# FPGA_ADC_USB_Board.net
KiCad netlist of a schematic drawn in EAGLE
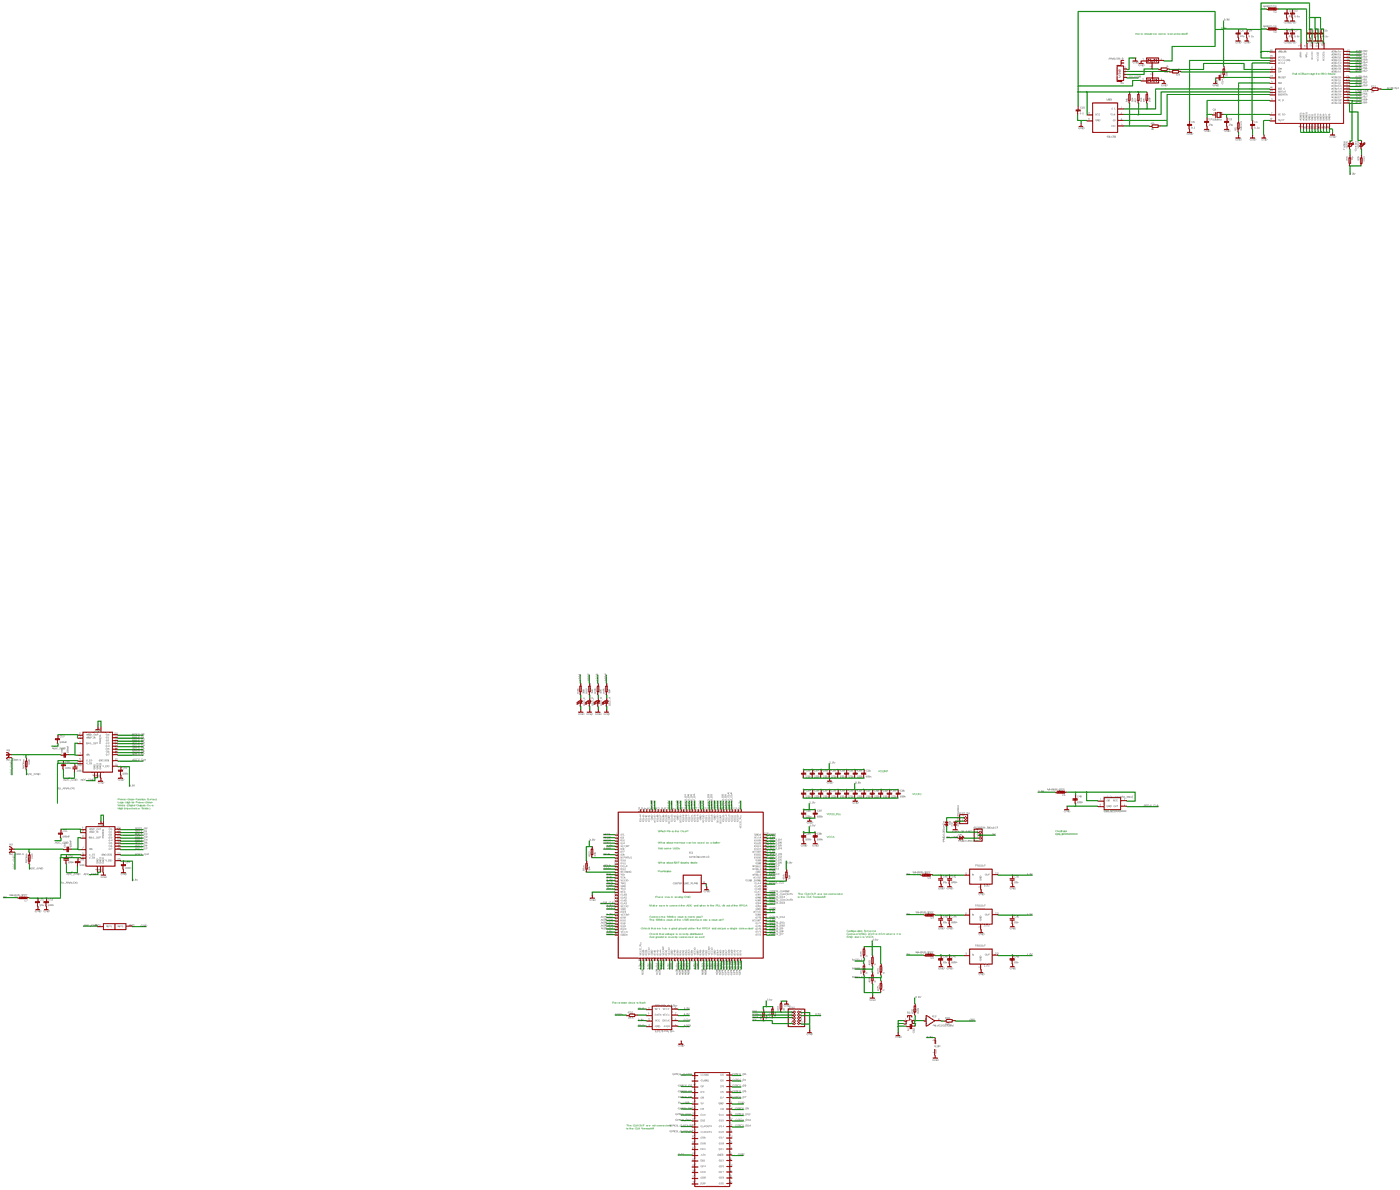
[diagram p0: schematic, sheet 1, overview]
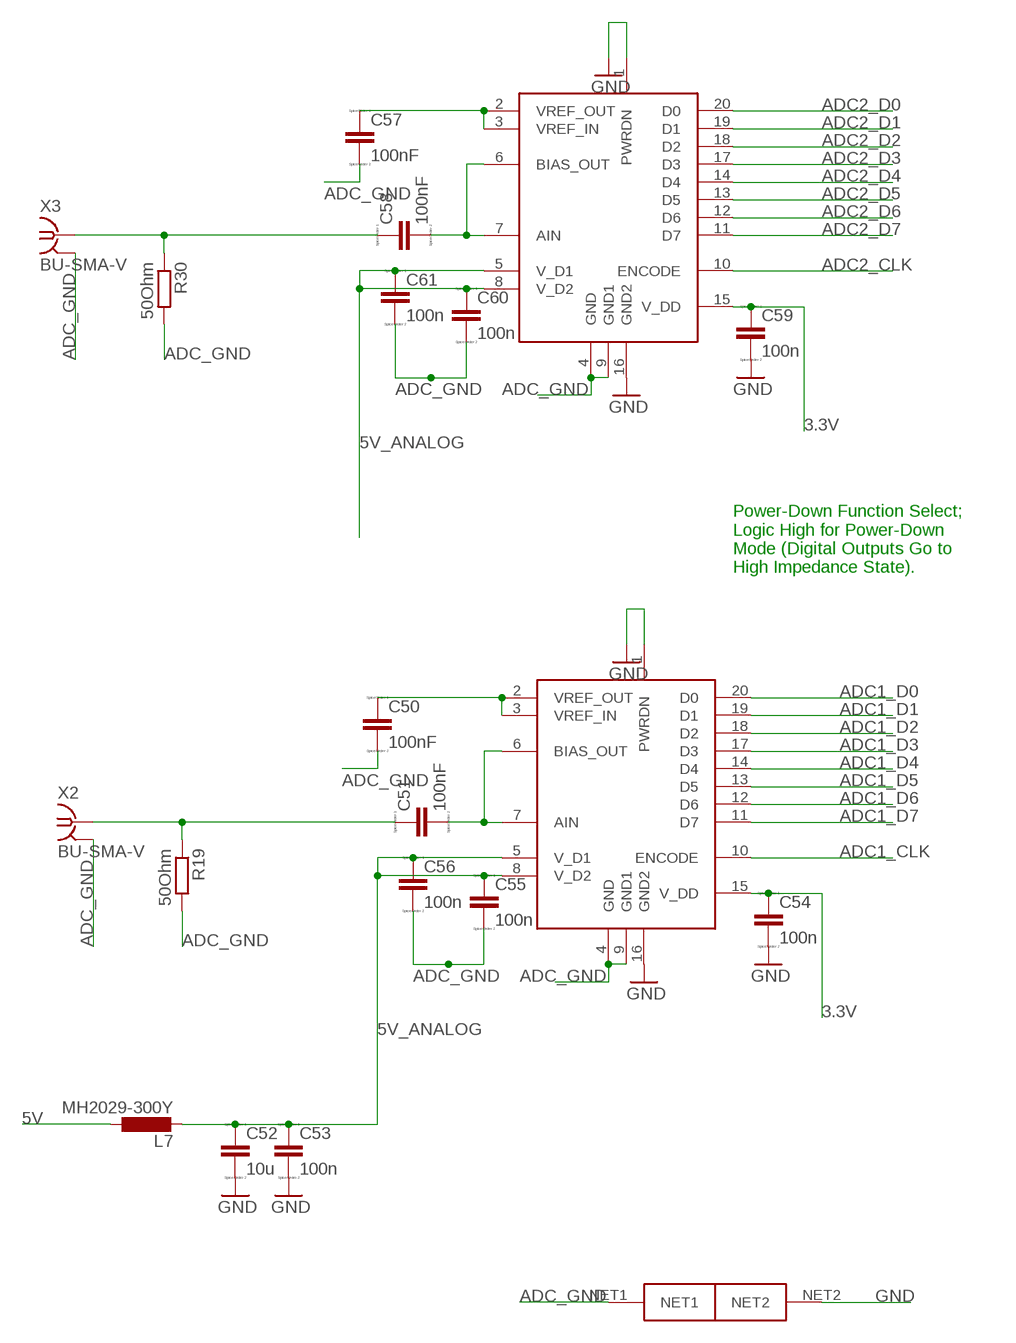
[diagram p1: schematic, sheet 1, part 1 of 4]
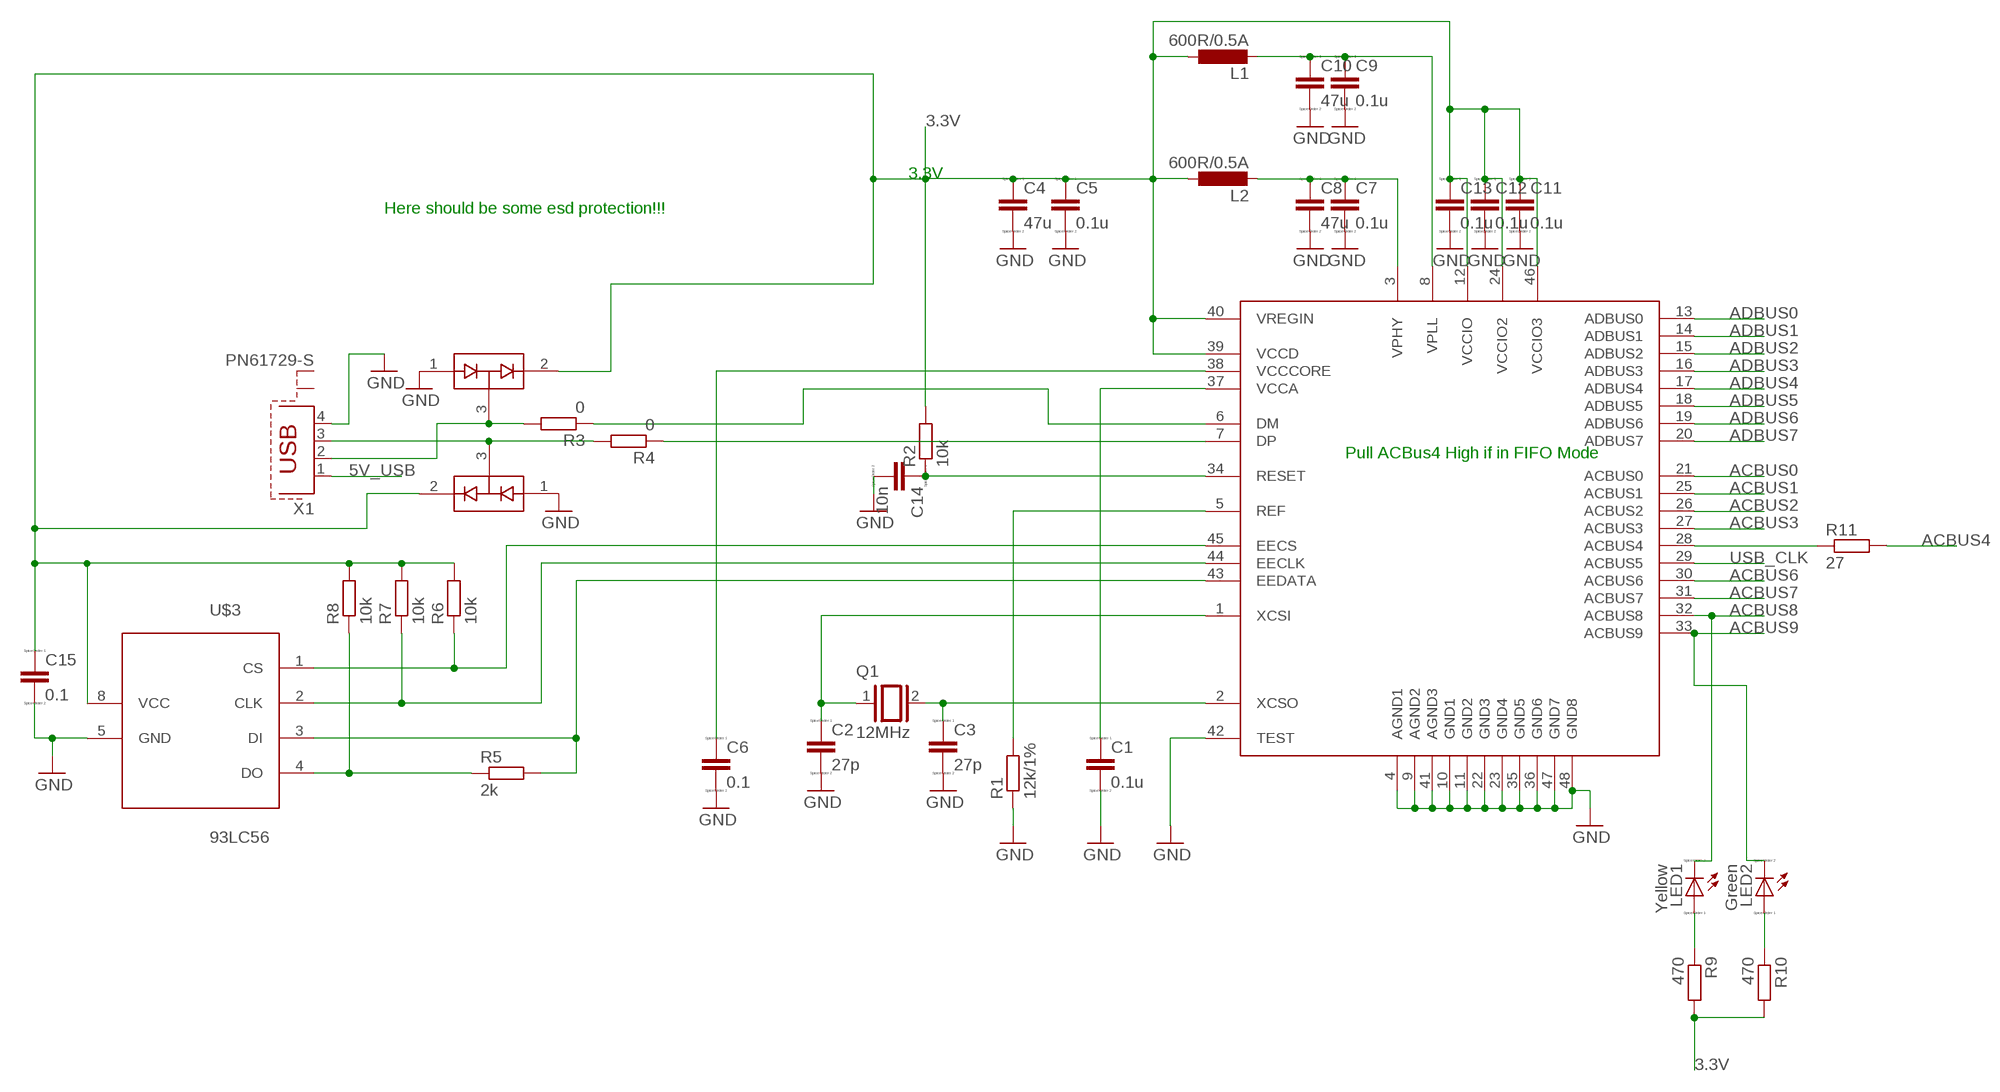
[diagram p2: schematic, sheet 1, part 2 of 4]
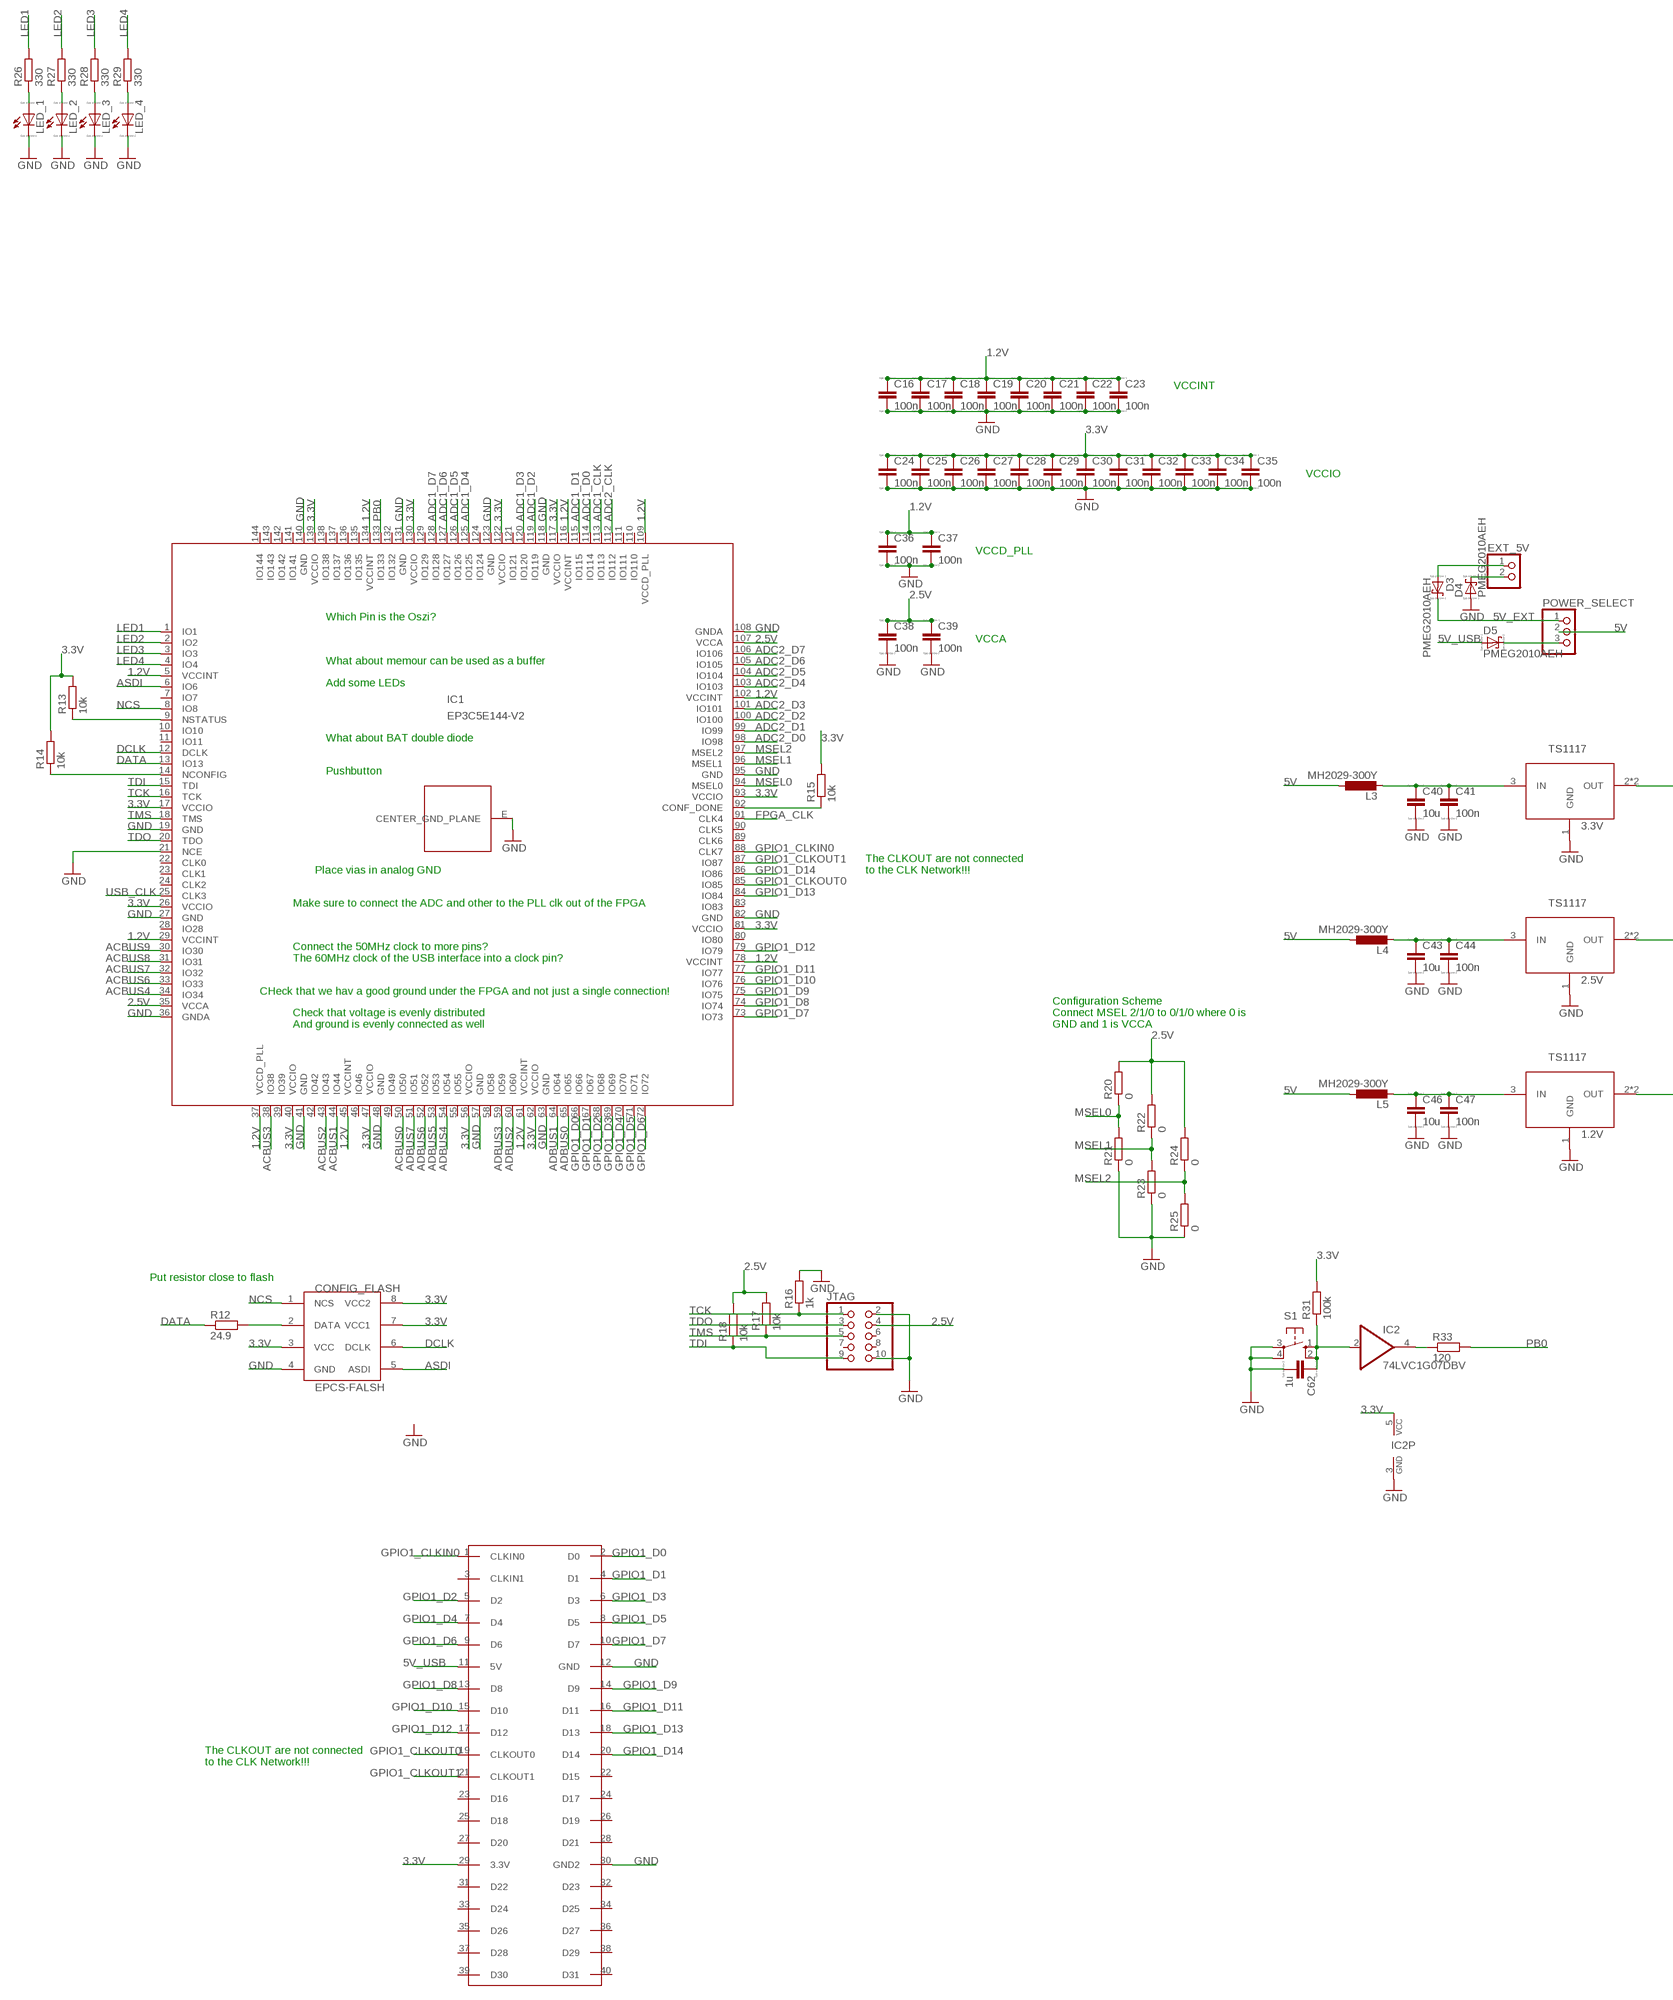
[diagram p3: schematic, sheet 1, part 3 of 4]
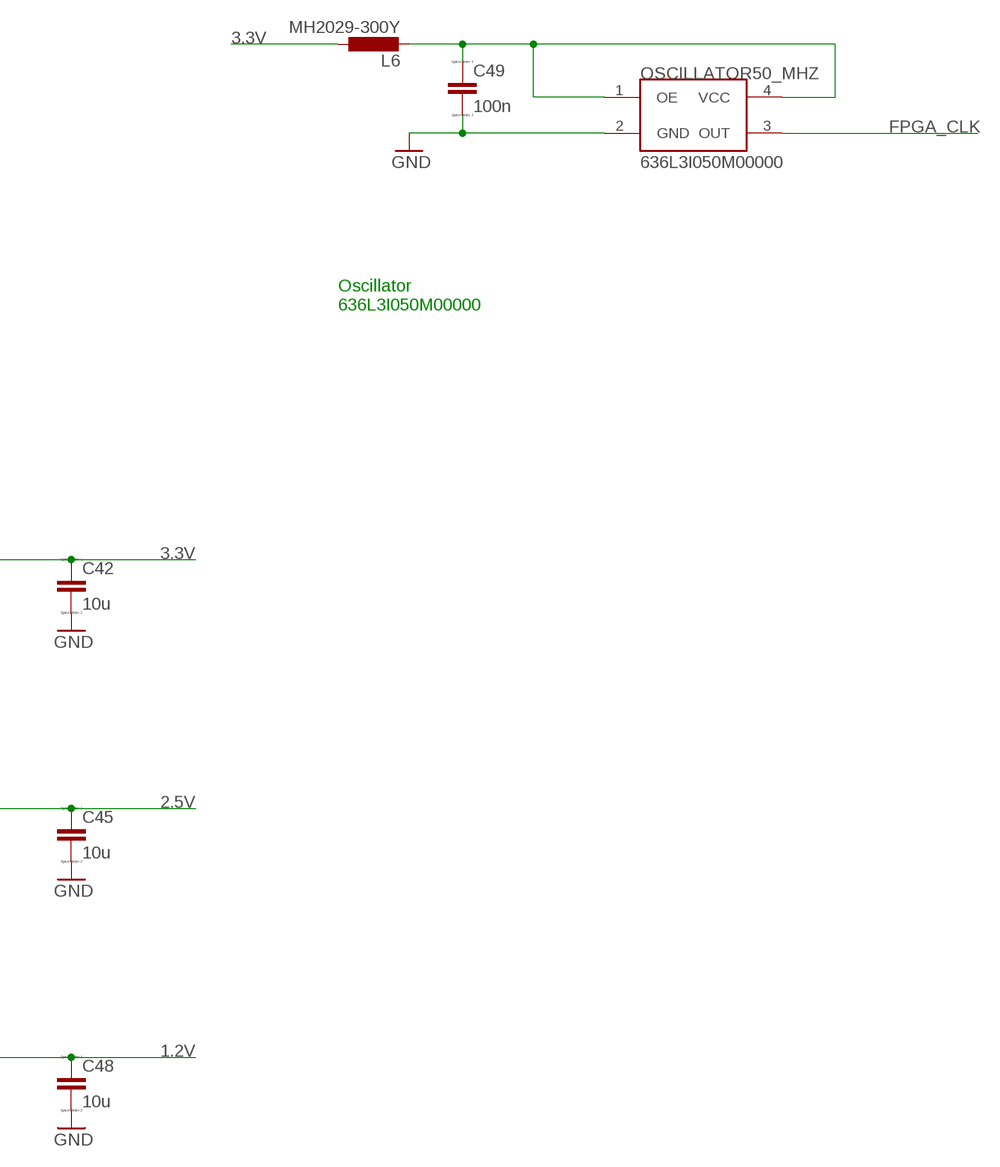
[diagram p4: schematic, sheet 1, part 4 of 4]

(export (version "E")
  (design (tool "Eeschema 10.0.6"))
  (components
    (comp (ref "C1")
      (value "0.1u")
      (footprint "eagle-import:C0805")
      (libsource (lib "eagle-import") (part "C_SMD"))
    )
    (comp (ref "C2")
      (value "27p")
      (footprint "eagle-import:C0805")
      (libsource (lib "eagle-import") (part "C_SMD"))
    )
    (comp (ref "C3")
      (value "27p")
      (footprint "eagle-import:C0805")
      (libsource (lib "eagle-import") (part "C_SMD"))
    )
    (comp (ref "C4")
      (value "47u")
      (footprint "eagle-import:C0805")
      (libsource (lib "eagle-import") (part "C_SMD"))
    )
    (comp (ref "C5")
      (value "0.1u")
      (footprint "eagle-import:C0805")
      (libsource (lib "eagle-import") (part "C_SMD"))
    )
    (comp (ref "C6")
      (value "0.1")
      (footprint "eagle-import:C0805")
      (libsource (lib "eagle-import") (part "C_SMD"))
    )
    (comp (ref "C7")
      (value "0.1u")
      (footprint "eagle-import:C0805")
      (libsource (lib "eagle-import") (part "C_SMD"))
    )
    (comp (ref "C8")
      (value "47u")
      (footprint "eagle-import:C0805")
      (libsource (lib "eagle-import") (part "C_SMD"))
    )
    (comp (ref "C9")
      (value "0.1u")
      (footprint "eagle-import:C0805")
      (libsource (lib "eagle-import") (part "C_SMD"))
    )
    (comp (ref "C10")
      (value "47u")
      (footprint "eagle-import:C0805")
      (libsource (lib "eagle-import") (part "C_SMD"))
    )
    (comp (ref "C11")
      (value "0.1u")
      (footprint "eagle-import:C0805")
      (libsource (lib "eagle-import") (part "C_SMD"))
    )
    (comp (ref "C12")
      (value "0.1u")
      (footprint "eagle-import:C0805")
      (libsource (lib "eagle-import") (part "C_SMD"))
    )
    (comp (ref "C13")
      (value "0.1u")
      (footprint "eagle-import:C0805")
      (libsource (lib "eagle-import") (part "C_SMD"))
    )
    (comp (ref "C14")
      (value "10n")
      (footprint "eagle-import:C0805")
      (libsource (lib "eagle-import") (part "C_SMD"))
    )
    (comp (ref "C15")
      (value "0.1")
      (footprint "eagle-import:C0805")
      (libsource (lib "eagle-import") (part "C_SMD"))
    )
    (comp (ref "C16")
      (value "100n")
      (footprint "eagle-import:C0805")
      (libsource (lib "eagle-import") (part "C_SMD"))
    )
    (comp (ref "C17")
      (value "100n")
      (footprint "eagle-import:C0805")
      (libsource (lib "eagle-import") (part "C_SMD"))
    )
    (comp (ref "C18")
      (value "100n")
      (footprint "eagle-import:C0805")
      (libsource (lib "eagle-import") (part "C_SMD"))
    )
    (comp (ref "C19")
      (value "100n")
      (footprint "eagle-import:C0805")
      (libsource (lib "eagle-import") (part "C_SMD"))
    )
    (comp (ref "C20")
      (value "100n")
      (footprint "eagle-import:C0805")
      (libsource (lib "eagle-import") (part "C_SMD"))
    )
    (comp (ref "C21")
      (value "100n")
      (footprint "eagle-import:C0805")
      (libsource (lib "eagle-import") (part "C_SMD"))
    )
    (comp (ref "C22")
      (value "100n")
      (footprint "eagle-import:C0805")
      (libsource (lib "eagle-import") (part "C_SMD"))
    )
    (comp (ref "C23")
      (value "100n")
      (footprint "eagle-import:C0805")
      (libsource (lib "eagle-import") (part "C_SMD"))
    )
    (comp (ref "C24")
      (value "100n")
      (footprint "eagle-import:C0805")
      (libsource (lib "eagle-import") (part "C_SMD"))
    )
    (comp (ref "C25")
      (value "100n")
      (footprint "eagle-import:C0805")
      (libsource (lib "eagle-import") (part "C_SMD"))
    )
    (comp (ref "C26")
      (value "100n")
      (footprint "eagle-import:C0805")
      (libsource (lib "eagle-import") (part "C_SMD"))
    )
    (comp (ref "C27")
      (value "100n")
      (footprint "eagle-import:C0805")
      (libsource (lib "eagle-import") (part "C_SMD"))
    )
    (comp (ref "C28")
      (value "100n")
      (footprint "eagle-import:C0805")
      (libsource (lib "eagle-import") (part "C_SMD"))
    )
    (comp (ref "C29")
      (value "100n")
      (footprint "eagle-import:C0805")
      (libsource (lib "eagle-import") (part "C_SMD"))
    )
    (comp (ref "C30")
      (value "100n")
      (footprint "eagle-import:C0805")
      (libsource (lib "eagle-import") (part "C_SMD"))
    )
    (comp (ref "C31")
      (value "100n")
      (footprint "eagle-import:C0805")
      (libsource (lib "eagle-import") (part "C_SMD"))
    )
    (comp (ref "C32")
      (value "100n")
      (footprint "eagle-import:C0805")
      (libsource (lib "eagle-import") (part "C_SMD"))
    )
    (comp (ref "C33")
      (value "100n")
      (footprint "eagle-import:C0805")
      (libsource (lib "eagle-import") (part "C_SMD"))
    )
    (comp (ref "C34")
      (value "100n")
      (footprint "eagle-import:C0805")
      (libsource (lib "eagle-import") (part "C_SMD"))
    )
    (comp (ref "C35")
      (value "100n")
      (footprint "eagle-import:C0805")
      (libsource (lib "eagle-import") (part "C_SMD"))
    )
    (comp (ref "C36")
      (value "100n")
      (footprint "eagle-import:C0805")
      (libsource (lib "eagle-import") (part "C_SMD"))
    )
    (comp (ref "C37")
      (value "100n")
      (footprint "eagle-import:C0805")
      (libsource (lib "eagle-import") (part "C_SMD"))
    )
    (comp (ref "C38")
      (value "100n")
      (footprint "eagle-import:C0805")
      (libsource (lib "eagle-import") (part "C_SMD"))
    )
    (comp (ref "C39")
      (value "100n")
      (footprint "eagle-import:C0805")
      (libsource (lib "eagle-import") (part "C_SMD"))
    )
    (comp (ref "C40")
      (value "10u")
      (footprint "eagle-import:C0805")
      (libsource (lib "eagle-import") (part "C_SMD"))
    )
    (comp (ref "C41")
      (value "100n")
      (footprint "eagle-import:C0805")
      (libsource (lib "eagle-import") (part "C_SMD"))
    )
    (comp (ref "C42")
      (value "10u")
      (footprint "eagle-import:C0805")
      (libsource (lib "eagle-import") (part "C_SMD"))
    )
    (comp (ref "C43")
      (value "10u")
      (footprint "eagle-import:C0805")
      (libsource (lib "eagle-import") (part "C_SMD"))
    )
    (comp (ref "C44")
      (value "100n")
      (footprint "eagle-import:C0805")
      (libsource (lib "eagle-import") (part "C_SMD"))
    )
    (comp (ref "C45")
      (value "10u")
      (footprint "eagle-import:C0805")
      (libsource (lib "eagle-import") (part "C_SMD"))
    )
    (comp (ref "C46")
      (value "10u")
      (footprint "eagle-import:C0805")
      (libsource (lib "eagle-import") (part "C_SMD"))
    )
    (comp (ref "C47")
      (value "100n")
      (footprint "eagle-import:C0805")
      (libsource (lib "eagle-import") (part "C_SMD"))
    )
    (comp (ref "C48")
      (value "10u")
      (footprint "eagle-import:C0805")
      (libsource (lib "eagle-import") (part "C_SMD"))
    )
    (comp (ref "C49")
      (value "100n")
      (footprint "eagle-import:C0805")
      (libsource (lib "eagle-import") (part "C_SMD"))
    )
    (comp (ref "C50")
      (value "100nF")
      (footprint "eagle-import:C0805")
      (libsource (lib "eagle-import") (part "C_SMD"))
    )
    (comp (ref "C51")
      (value "100nF")
      (footprint "eagle-import:C0805")
      (libsource (lib "eagle-import") (part "C_SMD"))
    )
    (comp (ref "C52")
      (value "10u")
      (footprint "eagle-import:C0805")
      (libsource (lib "eagle-import") (part "C_SMD"))
    )
    (comp (ref "C53")
      (value "100n")
      (footprint "eagle-import:C0805")
      (libsource (lib "eagle-import") (part "C_SMD"))
    )
    (comp (ref "C54")
      (value "100n")
      (footprint "eagle-import:C0805")
      (libsource (lib "eagle-import") (part "C_SMD"))
    )
    (comp (ref "C55")
      (value "100n")
      (footprint "eagle-import:C0805")
      (libsource (lib "eagle-import") (part "C_SMD"))
    )
    (comp (ref "C56")
      (value "100n")
      (footprint "eagle-import:C0805")
      (libsource (lib "eagle-import") (part "C_SMD"))
    )
    (comp (ref "C57")
      (value "100nF")
      (footprint "eagle-import:C0805")
      (libsource (lib "eagle-import") (part "C_SMD"))
    )
    (comp (ref "C58")
      (value "100nF")
      (footprint "eagle-import:C0805")
      (libsource (lib "eagle-import") (part "C_SMD"))
    )
    (comp (ref "C59")
      (value "100n")
      (footprint "eagle-import:C0805")
      (libsource (lib "eagle-import") (part "C_SMD"))
    )
    (comp (ref "C60")
      (value "100n")
      (footprint "eagle-import:C0805")
      (libsource (lib "eagle-import") (part "C_SMD"))
    )
    (comp (ref "C61")
      (value "100n")
      (footprint "eagle-import:C0805")
      (libsource (lib "eagle-import") (part "C_SMD"))
    )
    (comp (ref "C62")
      (value "1u")
      (footprint "eagle-import:C0805")
      (libsource (lib "eagle-import") (part "C_SMD"))
    )
    (comp (ref "CONFIG_FLASH")
      (value "EPCS-FALSH")
      (footprint "eagle-import:SO08")
      (libsource (lib "eagle-import") (part "EPCS-FALSH"))
    )
    (comp (ref "D1")
      (value "BAV99")
      (footprint "eagle-import:SOT23")
      (libsource (lib "eagle-import") (part "BAV99"))
    )
    (comp (ref "D2")
      (value "BAV99")
      (footprint "eagle-import:SOT23")
      (libsource (lib "eagle-import") (part "BAV99"))
    )
    (comp (ref "D3")
      (value "PMEG2010AEH")
      (footprint "eagle-import:SOD123")
      (libsource (lib "eagle-import") (part "PMEG2010AEH"))
    )
    (comp (ref "D4")
      (value "PMEG2010AEH")
      (footprint "eagle-import:SOD123")
      (libsource (lib "eagle-import") (part "PMEG2010AEH"))
    )
    (comp (ref "D5")
      (value "PMEG2010AEH")
      (footprint "eagle-import:SOD123")
      (libsource (lib "eagle-import") (part "PMEG2010AEH"))
    )
    (comp (ref "EXT_5V")
      (value "PINHD-1X2")
      (footprint "eagle-import:1X02")
      (libsource (lib "eagle-import") (part "PINHD-1X2"))
    )
    (comp (ref "IC1")
      (value "EP3C5E144-V2")
      (footprint "eagle-import:EQFP144")
      (libsource (lib "eagle-import") (part "EP3C5E144-V2"))
    )
    (comp (ref "IC2")
      (value "74LVC1G07DBV")
      (footprint "eagle-import:SOT23-5")
      (libsource (lib "eagle-import") (part "741G07DBVLVC"))
    )
    (comp (ref "JTAG")
      (value "PINHD-2X5")
      (footprint "eagle-import:2X05")
      (libsource (lib "eagle-import") (part "PINHD-2X5"))
    )
    (comp (ref "L1")
      (value "600R/0.5A")
      (footprint "eagle-import:R0805")
      (libsource (lib "eagle-import") (part "L_0805"))
    )
    (comp (ref "L2")
      (value "600R/0.5A")
      (footprint "eagle-import:R0805")
      (libsource (lib "eagle-import") (part "L_0805"))
    )
    (comp (ref "L3")
      (value "MH2029-300Y")
      (footprint "eagle-import:R0805")
      (libsource (lib "eagle-import") (part "L_0805"))
    )
    (comp (ref "L4")
      (value "MH2029-300Y")
      (footprint "eagle-import:R0805")
      (libsource (lib "eagle-import") (part "L_0805"))
    )
    (comp (ref "L5")
      (value "MH2029-300Y")
      (footprint "eagle-import:R0805")
      (libsource (lib "eagle-import") (part "L_0805"))
    )
    (comp (ref "L6")
      (value "MH2029-300Y")
      (footprint "eagle-import:R0805")
      (libsource (lib "eagle-import") (part "L_0805"))
    )
    (comp (ref "L7")
      (value "MH2029-300Y")
      (footprint "eagle-import:R0805")
      (libsource (lib "eagle-import") (part "L_0805"))
    )
    (comp (ref "LED1")
      (value "Yellow")
      (footprint "eagle-import:R0805")
      (libsource (lib "eagle-import") (part "LED_ELED_0805"))
    )
    (comp (ref "LED2")
      (value "Green")
      (footprint "eagle-import:R0805")
      (libsource (lib "eagle-import") (part "LED_ELED_0805"))
    )
    (comp (ref "LED_1")
      (value "LED_ELED_0805")
      (footprint "eagle-import:R0805")
      (libsource (lib "eagle-import") (part "LED_ELED_0805"))
    )
    (comp (ref "LED_2")
      (value "LED_ELED_0805")
      (footprint "eagle-import:R0805")
      (libsource (lib "eagle-import") (part "LED_ELED_0805"))
    )
    (comp (ref "LED_3")
      (value "LED_ELED_0805")
      (footprint "eagle-import:R0805")
      (libsource (lib "eagle-import") (part "LED_ELED_0805"))
    )
    (comp (ref "LED_4")
      (value "LED_ELED_0805")
      (footprint "eagle-import:R0805")
      (libsource (lib "eagle-import") (part "LED_ELED_0805"))
    )
    (comp (ref "LS")
      (value "3.3V")
      (footprint "eagle-import:SOT223")
      (libsource (lib "eagle-import") (part "TS1117"))
    )
    (comp (ref "OSCILLATOR50_MHZ")
      (value "636L3I050M00000")
      (footprint "eagle-import:OSZI_5X3.2")
      (libsource (lib "eagle-import") (part "OSZI"))
    )
    (comp (ref "POWER_SELECT")
      (value "PINHD-1X3")
      (footprint "eagle-import:1X03")
      (libsource (lib "eagle-import") (part "PINHD-1X3"))
    )
    (comp (ref "Q1")
      (value "12MHz")
      (footprint "eagle-import:QS")
      (libsource (lib "eagle-import") (part "XTAL/S"))
    )
    (comp (ref "R1")
      (value "12k/1%")
      (footprint "eagle-import:M0805")
      (libsource (lib "eagle-import") (part "R-EU_M0805"))
    )
    (comp (ref "R2")
      (value "10k")
      (footprint "eagle-import:M0805")
      (libsource (lib "eagle-import") (part "R-EU_M0805"))
    )
    (comp (ref "R3")
      (value "0")
      (footprint "eagle-import:M0805")
      (libsource (lib "eagle-import") (part "R-EU_M0805"))
    )
    (comp (ref "R4")
      (value "0")
      (footprint "eagle-import:M0805")
      (libsource (lib "eagle-import") (part "R-EU_M0805"))
    )
    (comp (ref "R5")
      (value "2k")
      (footprint "eagle-import:M0805")
      (libsource (lib "eagle-import") (part "R-EU_M0805"))
    )
    (comp (ref "R6")
      (value "10k")
      (footprint "eagle-import:M0805")
      (libsource (lib "eagle-import") (part "R-EU_M0805"))
    )
    (comp (ref "R7")
      (value "10k")
      (footprint "eagle-import:M0805")
      (libsource (lib "eagle-import") (part "R-EU_M0805"))
    )
    (comp (ref "R8")
      (value "10k")
      (footprint "eagle-import:M0805")
      (libsource (lib "eagle-import") (part "R-EU_M0805"))
    )
    (comp (ref "R9")
      (value "470")
      (footprint "eagle-import:M0805")
      (libsource (lib "eagle-import") (part "R-EU_M0805"))
    )
    (comp (ref "R10")
      (value "470")
      (footprint "eagle-import:M0805")
      (libsource (lib "eagle-import") (part "R-EU_M0805"))
    )
    (comp (ref "R11")
      (value "27")
      (footprint "eagle-import:M0805")
      (libsource (lib "eagle-import") (part "R-EU_M0805"))
    )
    (comp (ref "R12")
      (value "24.9")
      (footprint "eagle-import:R0805")
      (libsource (lib "eagle-import") (part "R-EU_R0805"))
    )
    (comp (ref "R13")
      (value "10k")
      (footprint "eagle-import:R0805")
      (libsource (lib "eagle-import") (part "R-EU_R0805"))
    )
    (comp (ref "R14")
      (value "10k")
      (footprint "eagle-import:R0805")
      (libsource (lib "eagle-import") (part "R-EU_R0805"))
    )
    (comp (ref "R15")
      (value "10k")
      (footprint "eagle-import:R0805")
      (libsource (lib "eagle-import") (part "R-EU_R0805"))
    )
    (comp (ref "R16")
      (value "1k")
      (footprint "eagle-import:R0805")
      (libsource (lib "eagle-import") (part "R-EU_R0805"))
    )
    (comp (ref "R17")
      (value "10k")
      (footprint "eagle-import:R0805")
      (libsource (lib "eagle-import") (part "R-EU_R0805"))
    )
    (comp (ref "R18")
      (value "10k")
      (footprint "eagle-import:R0805")
      (libsource (lib "eagle-import") (part "R-EU_R0805"))
    )
    (comp (ref "R19")
      (value "50Ohm")
      (footprint "eagle-import:R0805")
      (libsource (lib "eagle-import") (part "R-EU_R0805"))
    )
    (comp (ref "R20")
      (value "0")
      (footprint "eagle-import:R0805")
      (libsource (lib "eagle-import") (part "R-EU_R0805"))
    )
    (comp (ref "R21")
      (value "0")
      (footprint "eagle-import:R0805")
      (libsource (lib "eagle-import") (part "R-EU_R0805"))
    )
    (comp (ref "R22")
      (value "0")
      (footprint "eagle-import:R0805")
      (libsource (lib "eagle-import") (part "R-EU_R0805"))
    )
    (comp (ref "R23")
      (value "0")
      (footprint "eagle-import:R0805")
      (libsource (lib "eagle-import") (part "R-EU_R0805"))
    )
    (comp (ref "R24")
      (value "0")
      (footprint "eagle-import:R0805")
      (libsource (lib "eagle-import") (part "R-EU_R0805"))
    )
    (comp (ref "R25")
      (value "0")
      (footprint "eagle-import:R0805")
      (libsource (lib "eagle-import") (part "R-EU_R0805"))
    )
    (comp (ref "R26")
      (value "330")
      (footprint "eagle-import:R0805")
      (libsource (lib "eagle-import") (part "R-EU_R0805"))
    )
    (comp (ref "R27")
      (value "330")
      (footprint "eagle-import:R0805")
      (libsource (lib "eagle-import") (part "R-EU_R0805"))
    )
    (comp (ref "R28")
      (value "330")
      (footprint "eagle-import:R0805")
      (libsource (lib "eagle-import") (part "R-EU_R0805"))
    )
    (comp (ref "R29")
      (value "330")
      (footprint "eagle-import:R0805")
      (libsource (lib "eagle-import") (part "R-EU_R0805"))
    )
    (comp (ref "R30")
      (value "50Ohm")
      (footprint "eagle-import:R0805")
      (libsource (lib "eagle-import") (part "R-EU_R0805"))
    )
    (comp (ref "R31")
      (value "100k")
      (footprint "eagle-import:R0805")
      (libsource (lib "eagle-import") (part "R-EU_R0805"))
    )
    (comp (ref "R33")
      (value "120")
      (footprint "eagle-import:R0805")
      (libsource (lib "eagle-import") (part "R-EU_R0805"))
    )
    (comp (ref "S1")
      (value "10-XX")
      (footprint "eagle-import:B3F-10XX")
      (fields (field (name "MPN") "B3F-1000"))
      (libsource (lib "eagle-import") (part "10-XX"))
    )
    (comp (ref "U$1")
      (value "FT232H")
      (footprint "eagle-import:LQFP48")
      (libsource (lib "eagle-import") (part "FT232H"))
    )
    (comp (ref "U$2")
      (value "AD9057")
      (footprint "eagle-import:SSOP20")
      (libsource (lib "eagle-import") (part "AD9057"))
    )
    (comp (ref "U$3")
      (value "93LC56")
      (footprint "eagle-import:DIL-08")
      (libsource (lib "eagle-import") (part "93LC56"))
    )
    (comp (ref "U$4")
      (value "2.5V")
      (footprint "eagle-import:SOT223")
      (libsource (lib "eagle-import") (part "TS1117"))
    )
    (comp (ref "U$5")
      (value "1.2V")
      (footprint "eagle-import:SOT223")
      (libsource (lib "eagle-import") (part "TS1117"))
    )
    (comp (ref "U$6")
      (value "AD9057")
      (footprint "eagle-import:SSOP20")
      (libsource (lib "eagle-import") (part "AD9057"))
    )
    (comp (ref "U$7")
      (value "FPGA_GPIO_DE0")
      (footprint "eagle-import:2X20")
      (libsource (lib "eagle-import") (part "FPGA_GPIO_DE0"))
    )
    (comp (ref "U$8")
      (value "NET_TIE")
      (footprint "eagle-import:NET-TIE")
      (libsource (lib "eagle-import") (part "NET_TIE"))
    )
    (comp (ref "X1")
      (value "PN61729-S")
      (footprint "eagle-import:PN61729-S")
      (libsource (lib "eagle-import") (part "PN61729-S"))
    )
    (comp (ref "X2")
      (value "BU-SMA-V")
      (footprint "eagle-import:BU-SMA-V")
      (libsource (lib "eagle-import") (part "BU-SMA-V"))
    )
    (comp (ref "X3")
      (value "BU-SMA-V")
      (footprint "eagle-import:BU-SMA-V")
      (libsource (lib "eagle-import") (part "BU-SMA-V"))
    )
  )
  (nets
    (net (code "1") (name "/1.2V") (class "Default")
      (node (ref "C16") (pin "1") (pinfunction "1_1") (pintype "passive"))
      (node (ref "C17") (pin "1") (pinfunction "1_1") (pintype "passive"))
      (node (ref "C18") (pin "1") (pinfunction "1_1") (pintype "passive"))
      (node (ref "C19") (pin "1") (pinfunction "1_1") (pintype "passive"))
      (node (ref "C20") (pin "1") (pinfunction "1_1") (pintype "passive"))
      (node (ref "C21") (pin "1") (pinfunction "1_1") (pintype "passive"))
      (node (ref "C22") (pin "1") (pinfunction "1_1") (pintype "passive"))
      (node (ref "C23") (pin "1") (pinfunction "1_1") (pintype "passive"))
      (node (ref "C36") (pin "1") (pinfunction "1_1") (pintype "passive"))
      (node (ref "C37") (pin "1") (pinfunction "1_1") (pintype "passive"))
      (node (ref "C48") (pin "1") (pinfunction "1_1") (pintype "passive"))
      (node (ref "IC1") (pin "102") (pinfunction "VCCINT_102") (pintype "power_in"))
      (node (ref "IC1") (pin "109") (pinfunction "VCCD_PLL_109") (pintype "power_in"))
      (node (ref "IC1") (pin "116") (pinfunction "VCCINT_116") (pintype "power_in"))
      (node (ref "IC1") (pin "134") (pinfunction "VCCINT_134") (pintype "power_in"))
      (node (ref "IC1") (pin "29") (pinfunction "VCCINT_29") (pintype "power_in"))
      (node (ref "IC1") (pin "37") (pinfunction "VCCD_PLL_37") (pintype "power_in"))
      (node (ref "IC1") (pin "45") (pinfunction "VCCINT_45") (pintype "power_in"))
      (node (ref "IC1") (pin "5") (pinfunction "VCCINT_5") (pintype "power_in"))
      (node (ref "IC1") (pin "61") (pinfunction "VCCINT_61") (pintype "power_in"))
      (node (ref "IC1") (pin "78") (pinfunction "VCCINT_78") (pintype "power_in"))
      (node (ref "U$5") (pin "2") (pinfunction "OUT_2") (pintype "bidirectional"))
      (node (ref "U$5") (pin "4") (pinfunction "OUT_4") (pintype "bidirectional"))
    )
    (net (code "2") (name "/2.5V") (class "Default")
      (node (ref "C38") (pin "1") (pinfunction "1_1") (pintype "passive"))
      (node (ref "C39") (pin "1") (pinfunction "1_1") (pintype "passive"))
      (node (ref "C45") (pin "1") (pinfunction "1_1") (pintype "passive"))
      (node (ref "IC1") (pin "107") (pinfunction "VCCA_107") (pintype "power_in"))
      (node (ref "IC1") (pin "35") (pinfunction "VCCA_35") (pintype "power_in"))
      (node (ref "JTAG") (pin "4") (pinfunction "4_4") (pintype "passive"))
      (node (ref "R17") (pin "2") (pinfunction "2_2") (pintype "passive"))
      (node (ref "R18") (pin "2") (pinfunction "2_2") (pintype "passive"))
      (node (ref "R20") (pin "2") (pinfunction "2_2") (pintype "passive"))
      (node (ref "R22") (pin "2") (pinfunction "2_2") (pintype "passive"))
      (node (ref "R24") (pin "2") (pinfunction "2_2") (pintype "passive"))
      (node (ref "U$4") (pin "2") (pinfunction "OUT_2") (pintype "bidirectional"))
      (node (ref "U$4") (pin "4") (pinfunction "OUT_4") (pintype "bidirectional"))
    )
    (net (code "3") (name "/3.3V") (class "Default")
      (node (ref "C11") (pin "1") (pinfunction "1_1") (pintype "passive"))
      (node (ref "C12") (pin "1") (pinfunction "1_1") (pintype "passive"))
      (node (ref "C13") (pin "1") (pinfunction "1_1") (pintype "passive"))
      (node (ref "C15") (pin "1") (pinfunction "1_1") (pintype "passive"))
      (node (ref "C24") (pin "1") (pinfunction "1_1") (pintype "passive"))
      (node (ref "C25") (pin "1") (pinfunction "1_1") (pintype "passive"))
      (node (ref "C26") (pin "1") (pinfunction "1_1") (pintype "passive"))
      (node (ref "C27") (pin "1") (pinfunction "1_1") (pintype "passive"))
      (node (ref "C28") (pin "1") (pinfunction "1_1") (pintype "passive"))
      (node (ref "C29") (pin "1") (pinfunction "1_1") (pintype "passive"))
      (node (ref "C30") (pin "1") (pinfunction "1_1") (pintype "passive"))
      (node (ref "C31") (pin "1") (pinfunction "1_1") (pintype "passive"))
      (node (ref "C32") (pin "1") (pinfunction "1_1") (pintype "passive"))
      (node (ref "C33") (pin "1") (pinfunction "1_1") (pintype "passive"))
      (node (ref "C34") (pin "1") (pinfunction "1_1") (pintype "passive"))
      (node (ref "C35") (pin "1") (pinfunction "1_1") (pintype "passive"))
      (node (ref "C4") (pin "1") (pinfunction "1_1") (pintype "passive"))
      (node (ref "C42") (pin "1") (pinfunction "1_1") (pintype "passive"))
      (node (ref "C5") (pin "1") (pinfunction "1_1") (pintype "passive"))
      (node (ref "C54") (pin "1") (pinfunction "1_1") (pintype "passive"))
      (node (ref "C59") (pin "1") (pinfunction "1_1") (pintype "passive"))
      (node (ref "CONFIG_FLASH") (pin "3") (pinfunction "VCC_3") (pintype "bidirectional"))
      (node (ref "CONFIG_FLASH") (pin "7") (pinfunction "VCC1_7") (pintype "bidirectional"))
      (node (ref "CONFIG_FLASH") (pin "8") (pinfunction "VCC2_8") (pintype "bidirectional"))
      (node (ref "D1") (pin "2") (pinfunction "C2_2") (pintype "bidirectional"))
      (node (ref "D2") (pin "2") (pinfunction "C2_2") (pintype "bidirectional"))
      (node (ref "IC1") (pin "117") (pinfunction "VCCIO_117") (pintype "power_in"))
      (node (ref "IC1") (pin "122") (pinfunction "VCCIO_122") (pintype "power_in"))
      (node (ref "IC1") (pin "130") (pinfunction "VCCIO_130") (pintype "power_in"))
      (node (ref "IC1") (pin "139") (pinfunction "VCCIO_139") (pintype "power_in"))
      (node (ref "IC1") (pin "17") (pinfunction "VCCIO_17") (pintype "power_in"))
      (node (ref "IC1") (pin "26") (pinfunction "VCCIO_26") (pintype "power_in"))
      (node (ref "IC1") (pin "40") (pinfunction "VCCIO_40") (pintype "power_in"))
      (node (ref "IC1") (pin "47") (pinfunction "VCCIO_47") (pintype "power_in"))
      (node (ref "IC1") (pin "56") (pinfunction "VCCIO_56") (pintype "power_in"))
      (node (ref "IC1") (pin "62") (pinfunction "VCCIO_62") (pintype "power_in"))
      (node (ref "IC1") (pin "81") (pinfunction "VCCIO_81") (pintype "power_in"))
      (node (ref "IC1") (pin "93") (pinfunction "VCCIO_93") (pintype "power_in"))
      (node (ref "IC2") (pin "5") (pinfunction "VCC_5") (pintype "power_in"))
      (node (ref "L1") (pin "1") (pinfunction "1_1") (pintype "passive"))
      (node (ref "L2") (pin "1") (pinfunction "1_1") (pintype "passive"))
      (node (ref "L6") (pin "1") (pinfunction "1_1") (pintype "passive"))
      (node (ref "LS") (pin "2") (pinfunction "OUT_2") (pintype "bidirectional"))
      (node (ref "LS") (pin "4") (pinfunction "OUT_4") (pintype "bidirectional"))
      (node (ref "R10") (pin "2") (pinfunction "2_2") (pintype "passive"))
      (node (ref "R13") (pin "2") (pinfunction "2_2") (pintype "passive"))
      (node (ref "R14") (pin "2") (pinfunction "2_2") (pintype "passive"))
      (node (ref "R15") (pin "2") (pinfunction "2_2") (pintype "passive"))
      (node (ref "R2") (pin "2") (pinfunction "2_2") (pintype "passive"))
      (node (ref "R31") (pin "2") (pinfunction "2_2") (pintype "passive"))
      (node (ref "R6") (pin "2") (pinfunction "2_2") (pintype "passive"))
      (node (ref "R7") (pin "2") (pinfunction "2_2") (pintype "passive"))
      (node (ref "R8") (pin "2") (pinfunction "2_2") (pintype "passive"))
      (node (ref "R9") (pin "2") (pinfunction "2_2") (pintype "passive"))
      (node (ref "U$1") (pin "12") (pinfunction "VCCIO_12") (pintype "bidirectional"))
      (node (ref "U$1") (pin "24") (pinfunction "VCCIO2_24") (pintype "bidirectional"))
      (node (ref "U$1") (pin "39") (pinfunction "VCCD_39") (pintype "bidirectional"))
      (node (ref "U$1") (pin "40") (pinfunction "VREGIN_40") (pintype "bidirectional"))
      (node (ref "U$1") (pin "46") (pinfunction "VCCIO3_46") (pintype "bidirectional"))
      (node (ref "U$2") (pin "15") (pinfunction "V_DD_15") (pintype "bidirectional"))
      (node (ref "U$3") (pin "8") (pinfunction "VCC_8") (pintype "bidirectional"))
      (node (ref "U$6") (pin "15") (pinfunction "V_DD_15") (pintype "bidirectional"))
      (node (ref "U$7") (pin "29") (pinfunction "3.3V_29") (pintype "bidirectional"))
    )
    (net (code "4") (name "/5V") (class "Default")
      (node (ref "L3") (pin "1") (pinfunction "1_1") (pintype "passive"))
      (node (ref "L4") (pin "1") (pinfunction "1_1") (pintype "passive"))
      (node (ref "L5") (pin "1") (pinfunction "1_1") (pintype "passive"))
      (node (ref "L7") (pin "1") (pinfunction "1_1") (pintype "passive"))
      (node (ref "POWER_SELECT") (pin "2") (pinfunction "2_2") (pintype "passive"))
    )
    (net (code "5") (name "/5V_ANALOG") (class "Default")
      (node (ref "C52") (pin "1") (pinfunction "1_1") (pintype "passive"))
      (node (ref "C53") (pin "1") (pinfunction "1_1") (pintype "passive"))
      (node (ref "C55") (pin "1") (pinfunction "1_1") (pintype "passive"))
      (node (ref "C56") (pin "1") (pinfunction "1_1") (pintype "passive"))
      (node (ref "C60") (pin "1") (pinfunction "1_1") (pintype "passive"))
      (node (ref "C61") (pin "1") (pinfunction "1_1") (pintype "passive"))
      (node (ref "L7") (pin "2") (pinfunction "2_2") (pintype "passive"))
      (node (ref "U$2") (pin "5") (pinfunction "V_D1_5") (pintype "bidirectional"))
      (node (ref "U$2") (pin "8") (pinfunction "V_D2_8") (pintype "bidirectional"))
      (node (ref "U$6") (pin "5") (pinfunction "V_D1_5") (pintype "bidirectional"))
      (node (ref "U$6") (pin "8") (pinfunction "V_D2_8") (pintype "bidirectional"))
    )
    (net (code "6") (name "/5V_EXT") (class "Default")
      (node (ref "D3") (pin "1") (pinfunction "A_1") (pintype "passive"))
      (node (ref "POWER_SELECT") (pin "1") (pinfunction "1_1") (pintype "passive"))
    )
    (net (code "7") (name "/5V_USB") (class "Default")
      (node (ref "D5") (pin "2") (pinfunction "C_2") (pintype "passive"))
      (node (ref "U$7") (pin "11") (pinfunction "5V_11") (pintype "bidirectional"))
      (node (ref "X1") (pin "1") (pinfunction "1_1") (pintype "passive"))
    )
    (net (code "8") (name "/ACBUS0") (class "Default")
      (node (ref "IC1") (pin "50") (pinfunction "IO50_50") (pintype "bidirectional"))
      (node (ref "U$1") (pin "21") (pinfunction "ACBUS0_21") (pintype "bidirectional"))
    )
    (net (code "9") (name "/ACBUS1") (class "Default")
      (node (ref "IC1") (pin "44") (pinfunction "IO44_44") (pintype "bidirectional"))
      (node (ref "U$1") (pin "25") (pinfunction "ACBUS1_25") (pintype "bidirectional"))
    )
    (net (code "10") (name "/ACBUS2") (class "Default")
      (node (ref "IC1") (pin "43") (pinfunction "IO43_43") (pintype "bidirectional"))
      (node (ref "U$1") (pin "26") (pinfunction "ACBUS2_26") (pintype "bidirectional"))
    )
    (net (code "11") (name "/ACBUS3") (class "Default")
      (node (ref "IC1") (pin "38") (pinfunction "IO38_38") (pintype "bidirectional"))
      (node (ref "U$1") (pin "27") (pinfunction "ACBUS3_27") (pintype "bidirectional"))
    )
    (net (code "12") (name "/ACBUS4") (class "Default")
      (node (ref "IC1") (pin "34") (pinfunction "IO34_34") (pintype "bidirectional"))
      (node (ref "R11") (pin "2") (pinfunction "2_2") (pintype "passive"))
    )
    (net (code "13") (name "/ACBUS6") (class "Default")
      (node (ref "IC1") (pin "33") (pinfunction "IO33_33") (pintype "bidirectional"))
      (node (ref "U$1") (pin "30") (pinfunction "ACBUS6_30") (pintype "bidirectional"))
    )
    (net (code "14") (name "/ACBUS7") (class "Default")
      (node (ref "IC1") (pin "32") (pinfunction "IO32_32") (pintype "bidirectional"))
      (node (ref "U$1") (pin "31") (pinfunction "ACBUS7_31") (pintype "bidirectional"))
    )
    (net (code "15") (name "/ACBUS8") (class "Default")
      (node (ref "IC1") (pin "31") (pinfunction "IO31_31") (pintype "bidirectional"))
      (node (ref "LED1") (pin "2") (pinfunction "C_2") (pintype "passive"))
      (node (ref "U$1") (pin "32") (pinfunction "ACBUS8_32") (pintype "bidirectional"))
    )
    (net (code "16") (name "/ACBUS9") (class "Default")
      (node (ref "IC1") (pin "30") (pinfunction "IO30_30") (pintype "bidirectional"))
      (node (ref "LED2") (pin "2") (pinfunction "C_2") (pintype "passive"))
      (node (ref "U$1") (pin "33") (pinfunction "ACBUS9_33") (pintype "bidirectional"))
    )
    (net (code "17") (name "/ADBUS0") (class "Default")
      (node (ref "IC1") (pin "65") (pinfunction "IO65_65") (pintype "bidirectional"))
      (node (ref "U$1") (pin "13") (pinfunction "ADBUS0_13") (pintype "bidirectional"))
    )
    (net (code "18") (name "/ADBUS1") (class "Default")
      (node (ref "IC1") (pin "64") (pinfunction "IO64_64") (pintype "bidirectional"))
      (node (ref "U$1") (pin "14") (pinfunction "ADBUS1_14") (pintype "bidirectional"))
    )
    (net (code "19") (name "/ADBUS2") (class "Default")
      (node (ref "IC1") (pin "60") (pinfunction "IO60_60") (pintype "bidirectional"))
      (node (ref "U$1") (pin "15") (pinfunction "ADBUS2_15") (pintype "bidirectional"))
    )
    (net (code "20") (name "/ADBUS3") (class "Default")
      (node (ref "IC1") (pin "59") (pinfunction "IO59_59") (pintype "bidirectional"))
      (node (ref "U$1") (pin "16") (pinfunction "ADBUS3_16") (pintype "bidirectional"))
    )
    (net (code "21") (name "/ADBUS4") (class "Default")
      (node (ref "IC1") (pin "54") (pinfunction "IO54_54") (pintype "bidirectional"))
      (node (ref "U$1") (pin "17") (pinfunction "ADBUS4_17") (pintype "bidirectional"))
    )
    (net (code "22") (name "/ADBUS5") (class "Default")
      (node (ref "IC1") (pin "53") (pinfunction "IO53_53") (pintype "bidirectional"))
      (node (ref "U$1") (pin "18") (pinfunction "ADBUS5_18") (pintype "bidirectional"))
    )
    (net (code "23") (name "/ADBUS6") (class "Default")
      (node (ref "IC1") (pin "52") (pinfunction "IO52_52") (pintype "bidirectional"))
      (node (ref "U$1") (pin "19") (pinfunction "ADBUS6_19") (pintype "bidirectional"))
    )
    (net (code "24") (name "/ADBUS7") (class "Default")
      (node (ref "IC1") (pin "51") (pinfunction "IO51_51") (pintype "bidirectional"))
      (node (ref "U$1") (pin "20") (pinfunction "ADBUS7_20") (pintype "bidirectional"))
    )
    (net (code "25") (name "/ADC1_CLK") (class "Default")
      (node (ref "IC1") (pin "113") (pinfunction "IO113_113") (pintype "bidirectional"))
      (node (ref "U$6") (pin "10") (pinfunction "ENCODE_10") (pintype "bidirectional"))
    )
    (net (code "26") (name "/ADC1_D0") (class "Default")
      (node (ref "IC1") (pin "114") (pinfunction "IO114_114") (pintype "bidirectional"))
      (node (ref "U$6") (pin "20") (pinfunction "D0_20") (pintype "bidirectional"))
    )
    (net (code "27") (name "/ADC1_D1") (class "Default")
      (node (ref "IC1") (pin "115") (pinfunction "IO115_115") (pintype "bidirectional"))
      (node (ref "U$6") (pin "19") (pinfunction "D1_19") (pintype "bidirectional"))
    )
    (net (code "28") (name "/ADC1_D2") (class "Default")
      (node (ref "IC1") (pin "119") (pinfunction "IO119_119") (pintype "bidirectional"))
      (node (ref "U$6") (pin "18") (pinfunction "D2_18") (pintype "bidirectional"))
    )
    (net (code "29") (name "/ADC1_D3") (class "Default")
      (node (ref "IC1") (pin "120") (pinfunction "IO120_120") (pintype "bidirectional"))
      (node (ref "U$6") (pin "17") (pinfunction "D3_17") (pintype "bidirectional"))
    )
    (net (code "30") (name "/ADC1_D4") (class "Default")
      (node (ref "IC1") (pin "125") (pinfunction "IO125_125") (pintype "bidirectional"))
      (node (ref "U$6") (pin "14") (pinfunction "D4_14") (pintype "bidirectional"))
    )
    (net (code "31") (name "/ADC1_D5") (class "Default")
      (node (ref "IC1") (pin "126") (pinfunction "IO126_126") (pintype "bidirectional"))
      (node (ref "U$6") (pin "13") (pinfunction "D5_13") (pintype "bidirectional"))
    )
    (net (code "32") (name "/ADC1_D6") (class "Default")
      (node (ref "IC1") (pin "127") (pinfunction "IO127_127") (pintype "bidirectional"))
      (node (ref "U$6") (pin "12") (pinfunction "D6_12") (pintype "bidirectional"))
    )
    (net (code "33") (name "/ADC1_D7") (class "Default")
      (node (ref "IC1") (pin "128") (pinfunction "IO128_128") (pintype "bidirectional"))
      (node (ref "U$6") (pin "11") (pinfunction "D7_11") (pintype "bidirectional"))
    )
    (net (code "34") (name "/ADC2_CLK") (class "Default")
      (node (ref "IC1") (pin "112") (pinfunction "IO112_112") (pintype "bidirectional"))
      (node (ref "U$2") (pin "10") (pinfunction "ENCODE_10") (pintype "bidirectional"))
    )
    (net (code "35") (name "/ADC2_D0") (class "Default")
      (node (ref "IC1") (pin "98") (pinfunction "IO98_98") (pintype "bidirectional"))
      (node (ref "U$2") (pin "20") (pinfunction "D0_20") (pintype "bidirectional"))
    )
    (net (code "36") (name "/ADC2_D1") (class "Default")
      (node (ref "IC1") (pin "99") (pinfunction "IO99_99") (pintype "bidirectional"))
      (node (ref "U$2") (pin "19") (pinfunction "D1_19") (pintype "bidirectional"))
    )
    (net (code "37") (name "/ADC2_D2") (class "Default")
      (node (ref "IC1") (pin "100") (pinfunction "IO100_100") (pintype "bidirectional"))
      (node (ref "U$2") (pin "18") (pinfunction "D2_18") (pintype "bidirectional"))
    )
    (net (code "38") (name "/ADC2_D3") (class "Default")
      (node (ref "IC1") (pin "101") (pinfunction "IO101_101") (pintype "bidirectional"))
      (node (ref "U$2") (pin "17") (pinfunction "D3_17") (pintype "bidirectional"))
    )
    (net (code "39") (name "/ADC2_D4") (class "Default")
      (node (ref "IC1") (pin "103") (pinfunction "IO103_103") (pintype "bidirectional"))
      (node (ref "U$2") (pin "14") (pinfunction "D4_14") (pintype "bidirectional"))
    )
    (net (code "40") (name "/ADC2_D5") (class "Default")
      (node (ref "IC1") (pin "104") (pinfunction "IO104_104") (pintype "bidirectional"))
      (node (ref "U$2") (pin "13") (pinfunction "D5_13") (pintype "bidirectional"))
    )
    (net (code "41") (name "/ADC2_D6") (class "Default")
      (node (ref "IC1") (pin "105") (pinfunction "IO105_105") (pintype "bidirectional"))
      (node (ref "U$2") (pin "12") (pinfunction "D6_12") (pintype "bidirectional"))
    )
    (net (code "42") (name "/ADC2_D7") (class "Default")
      (node (ref "IC1") (pin "106") (pinfunction "IO106_106") (pintype "bidirectional"))
      (node (ref "U$2") (pin "11") (pinfunction "D7_11") (pintype "bidirectional"))
    )
    (net (code "43") (name "/ADC_GND") (class "Default")
      (node (ref "C50") (pin "2") (pinfunction "2_2") (pintype "passive"))
      (node (ref "C55") (pin "2") (pinfunction "2_2") (pintype "passive"))
      (node (ref "C56") (pin "2") (pinfunction "2_2") (pintype "passive"))
      (node (ref "C57") (pin "2") (pinfunction "2_2") (pintype "passive"))
      (node (ref "C60") (pin "2") (pinfunction "2_2") (pintype "passive"))
      (node (ref "C61") (pin "2") (pinfunction "2_2") (pintype "passive"))
      (node (ref "R19") (pin "2") (pinfunction "2_2") (pintype "passive"))
      (node (ref "R30") (pin "2") (pinfunction "2_2") (pintype "passive"))
      (node (ref "U$2") (pin "4") (pinfunction "GND_4") (pintype "bidirectional"))
      (node (ref "U$2") (pin "9") (pinfunction "GND1_9") (pintype "bidirectional"))
      (node (ref "U$6") (pin "4") (pinfunction "GND_4") (pintype "bidirectional"))
      (node (ref "U$6") (pin "9") (pinfunction "GND1_9") (pintype "bidirectional"))
      (node (ref "U$8") (pin "NET1") (pinfunction "NET1_NET1") (pintype "bidirectional"))
      (node (ref "X2") (pin "2") (pinfunction "2_2") (pintype "passive"))
      (node (ref "X2") (pin "3") (pinfunction "2_3") (pintype "passive"))
      (node (ref "X2") (pin "4") (pinfunction "2_4") (pintype "passive"))
      (node (ref "X2") (pin "5") (pinfunction "2_5") (pintype "passive"))
      (node (ref "X3") (pin "2") (pinfunction "2_2") (pintype "passive"))
      (node (ref "X3") (pin "3") (pinfunction "2_3") (pintype "passive"))
      (node (ref "X3") (pin "4") (pinfunction "2_4") (pintype "passive"))
      (node (ref "X3") (pin "5") (pinfunction "2_5") (pintype "passive"))
    )
    (net (code "44") (name "/ASDI") (class "Default")
      (node (ref "CONFIG_FLASH") (pin "5") (pinfunction "ASDI_5") (pintype "bidirectional"))
      (node (ref "IC1") (pin "6") (pinfunction "IO6_6") (pintype "passive"))
    )
    (net (code "45") (name "/DATA") (class "Default")
      (node (ref "IC1") (pin "13") (pinfunction "IO13_13") (pintype "bidirectional"))
      (node (ref "R12") (pin "1") (pinfunction "1_1") (pintype "passive"))
    )
    (net (code "46") (name "/DCLK") (class "Default")
      (node (ref "CONFIG_FLASH") (pin "6") (pinfunction "DCLK_6") (pintype "bidirectional"))
      (node (ref "IC1") (pin "12") (pinfunction "DCLK_12") (pintype "passive"))
    )
    (net (code "47") (name "/FPGA_CLK") (class "Default")
      (node (ref "IC1") (pin "91") (pinfunction "CLK4_91") (pintype "passive"))
      (node (ref "OSCILLATOR50_MHZ") (pin "3") (pinfunction "OUT_3") (pintype "bidirectional"))
    )
    (net (code "48") (name "/GPIO1_CLKIN0") (class "Default")
      (node (ref "IC1") (pin "88") (pinfunction "CLK7_88") (pintype "passive"))
      (node (ref "U$7") (pin "1") (pinfunction "CLKIN0_1") (pintype "bidirectional"))
    )
    (net (code "49") (name "/GPIO1_CLKOUT0") (class "Default")
      (node (ref "IC1") (pin "85") (pinfunction "IO85_85") (pintype "bidirectional"))
      (node (ref "U$7") (pin "19") (pinfunction "CLKOUT0_19") (pintype "bidirectional"))
    )
    (net (code "50") (name "/GPIO1_CLKOUT1") (class "Default")
      (node (ref "IC1") (pin "87") (pinfunction "IO87_87") (pintype "bidirectional"))
      (node (ref "U$7") (pin "21") (pinfunction "CLKOUT1_21") (pintype "bidirectional"))
    )
    (net (code "51") (name "/GPIO1_D0") (class "Default")
      (node (ref "IC1") (pin "66") (pinfunction "IO66_66") (pintype "bidirectional"))
      (node (ref "U$7") (pin "2") (pinfunction "D0_2") (pintype "bidirectional"))
    )
    (net (code "52") (name "/GPIO1_D1") (class "Default")
      (node (ref "IC1") (pin "67") (pinfunction "IO67_67") (pintype "bidirectional"))
      (node (ref "U$7") (pin "4") (pinfunction "D1_4") (pintype "bidirectional"))
    )
    (net (code "53") (name "/GPIO1_D2") (class "Default")
      (node (ref "IC1") (pin "68") (pinfunction "IO68_68") (pintype "bidirectional"))
      (node (ref "U$7") (pin "5") (pinfunction "D2_5") (pintype "bidirectional"))
    )
    (net (code "54") (name "/GPIO1_D3") (class "Default")
      (node (ref "IC1") (pin "69") (pinfunction "IO69_69") (pintype "bidirectional"))
      (node (ref "U$7") (pin "6") (pinfunction "D3_6") (pintype "bidirectional"))
    )
    (net (code "55") (name "/GPIO1_D4") (class "Default")
      (node (ref "IC1") (pin "70") (pinfunction "IO70_70") (pintype "bidirectional"))
      (node (ref "U$7") (pin "7") (pinfunction "D4_7") (pintype "bidirectional"))
    )
    (net (code "56") (name "/GPIO1_D5") (class "Default")
      (node (ref "IC1") (pin "71") (pinfunction "IO71_71") (pintype "bidirectional"))
      (node (ref "U$7") (pin "8") (pinfunction "D5_8") (pintype "bidirectional"))
    )
    (net (code "57") (name "/GPIO1_D6") (class "Default")
      (node (ref "IC1") (pin "72") (pinfunction "IO72_72") (pintype "bidirectional"))
      (node (ref "U$7") (pin "9") (pinfunction "D6_9") (pintype "bidirectional"))
    )
    (net (code "58") (name "/GPIO1_D7") (class "Default")
      (node (ref "IC1") (pin "73") (pinfunction "IO73_73") (pintype "bidirectional"))
      (node (ref "U$7") (pin "10") (pinfunction "D7_10") (pintype "bidirectional"))
    )
    (net (code "59") (name "/GPIO1_D8") (class "Default")
      (node (ref "IC1") (pin "74") (pinfunction "IO74_74") (pintype "bidirectional"))
      (node (ref "U$7") (pin "13") (pinfunction "D8_13") (pintype "bidirectional"))
    )
    (net (code "60") (name "/GPIO1_D9") (class "Default")
      (node (ref "IC1") (pin "75") (pinfunction "IO75_75") (pintype "bidirectional"))
      (node (ref "U$7") (pin "14") (pinfunction "D9_14") (pintype "bidirectional"))
    )
    (net (code "61") (name "/GPIO1_D10") (class "Default")
      (node (ref "IC1") (pin "76") (pinfunction "IO76_76") (pintype "bidirectional"))
      (node (ref "U$7") (pin "15") (pinfunction "D10_15") (pintype "bidirectional"))
    )
    (net (code "62") (name "/GPIO1_D11") (class "Default")
      (node (ref "IC1") (pin "77") (pinfunction "IO77_77") (pintype "bidirectional"))
      (node (ref "U$7") (pin "16") (pinfunction "D11_16") (pintype "bidirectional"))
    )
    (net (code "63") (name "/GPIO1_D12") (class "Default")
      (node (ref "IC1") (pin "79") (pinfunction "IO79_79") (pintype "bidirectional"))
      (node (ref "U$7") (pin "17") (pinfunction "D12_17") (pintype "bidirectional"))
    )
    (net (code "64") (name "/GPIO1_D13") (class "Default")
      (node (ref "IC1") (pin "84") (pinfunction "IO84_84") (pintype "bidirectional"))
      (node (ref "U$7") (pin "18") (pinfunction "D13_18") (pintype "bidirectional"))
    )
    (net (code "65") (name "/GPIO1_D14") (class "Default")
      (node (ref "IC1") (pin "86") (pinfunction "IO86_86") (pintype "bidirectional"))
      (node (ref "U$7") (pin "20") (pinfunction "D14_20") (pintype "bidirectional"))
    )
    (net (code "66") (name "/LED1") (class "Default")
      (node (ref "IC1") (pin "1") (pinfunction "IO1_1") (pintype "passive"))
      (node (ref "R26") (pin "2") (pinfunction "2_2") (pintype "passive"))
    )
    (net (code "67") (name "/LED2") (class "Default")
      (node (ref "IC1") (pin "2") (pinfunction "IO2_2") (pintype "passive"))
      (node (ref "R27") (pin "2") (pinfunction "2_2") (pintype "passive"))
    )
    (net (code "68") (name "/LED3") (class "Default")
      (node (ref "IC1") (pin "3") (pinfunction "IO3_3") (pintype "passive"))
      (node (ref "R28") (pin "2") (pinfunction "2_2") (pintype "passive"))
    )
    (net (code "69") (name "/LED4") (class "Default")
      (node (ref "IC1") (pin "4") (pinfunction "IO4_4") (pintype "passive"))
      (node (ref "R29") (pin "2") (pinfunction "2_2") (pintype "passive"))
    )
    (net (code "70") (name "/MSEL0") (class "Default")
      (node (ref "IC1") (pin "94") (pinfunction "MSEL0_94") (pintype "input"))
      (node (ref "R20") (pin "1") (pinfunction "1_1") (pintype "passive"))
      (node (ref "R21") (pin "2") (pinfunction "2_2") (pintype "passive"))
    )
    (net (code "71") (name "/MSEL1") (class "Default")
      (node (ref "IC1") (pin "96") (pinfunction "MSEL1_96") (pintype "input"))
      (node (ref "R22") (pin "1") (pinfunction "1_1") (pintype "passive"))
      (node (ref "R23") (pin "2") (pinfunction "2_2") (pintype "passive"))
    )
    (net (code "72") (name "/MSEL2") (class "Default")
      (node (ref "IC1") (pin "97") (pinfunction "MSEL2_97") (pintype "input"))
      (node (ref "R24") (pin "1") (pinfunction "1_1") (pintype "passive"))
      (node (ref "R25") (pin "2") (pinfunction "2_2") (pintype "passive"))
    )
    (net (code "73") (name "/NCS") (class "Default")
      (node (ref "CONFIG_FLASH") (pin "1") (pinfunction "NCS_1") (pintype "bidirectional"))
      (node (ref "IC1") (pin "8") (pinfunction "IO8_8") (pintype "output"))
    )
    (net (code "74") (name "/PB0") (class "Default")
      (node (ref "IC1") (pin "133") (pinfunction "IO133_133") (pintype "bidirectional"))
      (node (ref "R33") (pin "2") (pinfunction "2_2") (pintype "passive"))
    )
    (net (code "75") (name "/TCK") (class "Default")
      (node (ref "IC1") (pin "16") (pinfunction "TCK_16") (pintype "input"))
      (node (ref "JTAG") (pin "1") (pinfunction "1_1") (pintype "passive"))
      (node (ref "R16") (pin "1") (pinfunction "1_1") (pintype "passive"))
    )
    (net (code "76") (name "/TDI") (class "Default")
      (node (ref "IC1") (pin "15") (pinfunction "TDI_15") (pintype "input"))
      (node (ref "JTAG") (pin "9") (pinfunction "9_9") (pintype "passive"))
      (node (ref "R18") (pin "1") (pinfunction "1_1") (pintype "passive"))
    )
    (net (code "77") (name "/TDO") (class "Default")
      (node (ref "IC1") (pin "20") (pinfunction "TDO_20") (pintype "output"))
      (node (ref "JTAG") (pin "3") (pinfunction "3_3") (pintype "passive"))
    )
    (net (code "78") (name "/TMS") (class "Default")
      (node (ref "IC1") (pin "18") (pinfunction "TMS_18") (pintype "input"))
      (node (ref "JTAG") (pin "5") (pinfunction "5_5") (pintype "passive"))
      (node (ref "R17") (pin "1") (pinfunction "1_1") (pintype "passive"))
    )
    (net (code "79") (name "/USB_CLK") (class "Default")
      (node (ref "IC1") (pin "25") (pinfunction "CLK3_25") (pintype "passive"))
      (node (ref "U$1") (pin "29") (pinfunction "ACBUS5_29") (pintype "bidirectional"))
    )
    (net (code "80") (name "GND") (class "Default")
      (node (ref "C1") (pin "2") (pinfunction "2_2") (pintype "passive"))
      (node (ref "C10") (pin "2") (pinfunction "2_2") (pintype "passive"))
      (node (ref "C11") (pin "2") (pinfunction "2_2") (pintype "passive"))
      (node (ref "C12") (pin "2") (pinfunction "2_2") (pintype "passive"))
      (node (ref "C13") (pin "2") (pinfunction "2_2") (pintype "passive"))
      (node (ref "C14") (pin "2") (pinfunction "2_2") (pintype "passive"))
      (node (ref "C15") (pin "2") (pinfunction "2_2") (pintype "passive"))
      (node (ref "C16") (pin "2") (pinfunction "2_2") (pintype "passive"))
      (node (ref "C17") (pin "2") (pinfunction "2_2") (pintype "passive"))
      (node (ref "C18") (pin "2") (pinfunction "2_2") (pintype "passive"))
      (node (ref "C19") (pin "2") (pinfunction "2_2") (pintype "passive"))
      (node (ref "C2") (pin "2") (pinfunction "2_2") (pintype "passive"))
      (node (ref "C20") (pin "2") (pinfunction "2_2") (pintype "passive"))
      (node (ref "C21") (pin "2") (pinfunction "2_2") (pintype "passive"))
      (node (ref "C22") (pin "2") (pinfunction "2_2") (pintype "passive"))
      (node (ref "C23") (pin "2") (pinfunction "2_2") (pintype "passive"))
      (node (ref "C24") (pin "2") (pinfunction "2_2") (pintype "passive"))
      (node (ref "C25") (pin "2") (pinfunction "2_2") (pintype "passive"))
      (node (ref "C26") (pin "2") (pinfunction "2_2") (pintype "passive"))
      (node (ref "C27") (pin "2") (pinfunction "2_2") (pintype "passive"))
      (node (ref "C28") (pin "2") (pinfunction "2_2") (pintype "passive"))
      (node (ref "C29") (pin "2") (pinfunction "2_2") (pintype "passive"))
      (node (ref "C3") (pin "2") (pinfunction "2_2") (pintype "passive"))
      (node (ref "C30") (pin "2") (pinfunction "2_2") (pintype "passive"))
      (node (ref "C31") (pin "2") (pinfunction "2_2") (pintype "passive"))
      (node (ref "C32") (pin "2") (pinfunction "2_2") (pintype "passive"))
      (node (ref "C33") (pin "2") (pinfunction "2_2") (pintype "passive"))
      (node (ref "C34") (pin "2") (pinfunction "2_2") (pintype "passive"))
      (node (ref "C35") (pin "2") (pinfunction "2_2") (pintype "passive"))
      (node (ref "C36") (pin "2") (pinfunction "2_2") (pintype "passive"))
      (node (ref "C37") (pin "2") (pinfunction "2_2") (pintype "passive"))
      (node (ref "C38") (pin "2") (pinfunction "2_2") (pintype "passive"))
      (node (ref "C39") (pin "2") (pinfunction "2_2") (pintype "passive"))
      (node (ref "C4") (pin "2") (pinfunction "2_2") (pintype "passive"))
      (node (ref "C40") (pin "2") (pinfunction "2_2") (pintype "passive"))
      (node (ref "C41") (pin "2") (pinfunction "2_2") (pintype "passive"))
      (node (ref "C42") (pin "2") (pinfunction "2_2") (pintype "passive"))
      (node (ref "C43") (pin "2") (pinfunction "2_2") (pintype "passive"))
      (node (ref "C44") (pin "2") (pinfunction "2_2") (pintype "passive"))
      (node (ref "C45") (pin "2") (pinfunction "2_2") (pintype "passive"))
      (node (ref "C46") (pin "2") (pinfunction "2_2") (pintype "passive"))
      (node (ref "C47") (pin "2") (pinfunction "2_2") (pintype "passive"))
      (node (ref "C48") (pin "2") (pinfunction "2_2") (pintype "passive"))
      (node (ref "C49") (pin "2") (pinfunction "2_2") (pintype "passive"))
      (node (ref "C5") (pin "2") (pinfunction "2_2") (pintype "passive"))
      (node (ref "C52") (pin "2") (pinfunction "2_2") (pintype "passive"))
      (node (ref "C53") (pin "2") (pinfunction "2_2") (pintype "passive"))
      (node (ref "C54") (pin "2") (pinfunction "2_2") (pintype "passive"))
      (node (ref "C59") (pin "2") (pinfunction "2_2") (pintype "passive"))
      (node (ref "C6") (pin "2") (pinfunction "2_2") (pintype "passive"))
      (node (ref "C62") (pin "2") (pinfunction "2_2") (pintype "passive"))
      (node (ref "C7") (pin "2") (pinfunction "2_2") (pintype "passive"))
      (node (ref "C8") (pin "2") (pinfunction "2_2") (pintype "passive"))
      (node (ref "C9") (pin "2") (pinfunction "2_2") (pintype "passive"))
      (node (ref "CONFIG_FLASH") (pin "4") (pinfunction "GND_4") (pintype "bidirectional"))
      (node (ref "D1") (pin "1") (pinfunction "A1_1") (pintype "bidirectional"))
      (node (ref "D2") (pin "1") (pinfunction "A1_1") (pintype "bidirectional"))
      (node (ref "D4") (pin "2") (pinfunction "C_2") (pintype "passive"))
      (node (ref "IC1") (pin "108") (pinfunction "GNDA_108") (pintype "power_in"))
      (node (ref "IC1") (pin "118") (pinfunction "GND_118") (pintype "power_in"))
      (node (ref "IC1") (pin "123") (pinfunction "GND_123") (pintype "power_in"))
      (node (ref "IC1") (pin "131") (pinfunction "GND_131") (pintype "power_in"))
      (node (ref "IC1") (pin "140") (pinfunction "GND_140") (pintype "power_in"))
      (node (ref "IC1") (pin "19") (pinfunction "GND_19") (pintype "power_in"))
      (node (ref "IC1") (pin "21") (pinfunction "NCE_21") (pintype "input"))
      (node (ref "IC1") (pin "27") (pinfunction "GND_27") (pintype "power_in"))
      (node (ref "IC1") (pin "36") (pinfunction "GNDA_36") (pintype "power_in"))
      (node (ref "IC1") (pin "41") (pinfunction "GND_41") (pintype "power_in"))
      (node (ref "IC1") (pin "48") (pinfunction "GND_48") (pintype "power_in"))
      (node (ref "IC1") (pin "57") (pinfunction "GND_57") (pintype "power_in"))
      (node (ref "IC1") (pin "63") (pinfunction "GND_63") (pintype "power_in"))
      (node (ref "IC1") (pin "82") (pinfunction "GND_82") (pintype "power_in"))
      (node (ref "IC1") (pin "95") (pinfunction "GND_95") (pintype "power_in"))
      (node (ref "IC1") (pin "E") (pinfunction "CENTER_GND_PLANE_E") (pintype "bidirectional"))
      (node (ref "IC2") (pin "3") (pinfunction "GND_3") (pintype "power_in"))
      (node (ref "JTAG") (pin "10") (pinfunction "10_10") (pintype "passive"))
      (node (ref "JTAG") (pin "2") (pinfunction "2_2") (pintype "passive"))
      (node (ref "LED_1") (pin "2") (pinfunction "C_2") (pintype "passive"))
      (node (ref "LED_2") (pin "2") (pinfunction "C_2") (pintype "passive"))
      (node (ref "LED_3") (pin "2") (pinfunction "C_2") (pintype "passive"))
      (node (ref "LED_4") (pin "2") (pinfunction "C_2") (pintype "passive"))
      (node (ref "LS") (pin "1") (pinfunction "GND_1") (pintype "bidirectional"))
      (node (ref "OSCILLATOR50_MHZ") (pin "2") (pinfunction "GND_2") (pintype "bidirectional"))
      (node (ref "R1") (pin "1") (pinfunction "1_1") (pintype "passive"))
      (node (ref "R16") (pin "2") (pinfunction "2_2") (pintype "passive"))
      (node (ref "R21") (pin "1") (pinfunction "1_1") (pintype "passive"))
      (node (ref "R23") (pin "1") (pinfunction "1_1") (pintype "passive"))
      (node (ref "R25") (pin "1") (pinfunction "1_1") (pintype "passive"))
      (node (ref "S1") (pin "3") (pinfunction "P_3") (pintype "passive"))
      (node (ref "S1") (pin "4") (pinfunction "P1_4") (pintype "passive"))
      (node (ref "U$1") (pin "10") (pinfunction "GND1_10") (pintype "bidirectional"))
      (node (ref "U$1") (pin "11") (pinfunction "GND2_11") (pintype "bidirectional"))
      (node (ref "U$1") (pin "22") (pinfunction "GND3_22") (pintype "bidirectional"))
      (node (ref "U$1") (pin "23") (pinfunction "GND4_23") (pintype "bidirectional"))
      (node (ref "U$1") (pin "35") (pinfunction "GND5_35") (pintype "bidirectional"))
      (node (ref "U$1") (pin "36") (pinfunction "GND6_36") (pintype "bidirectional"))
      (node (ref "U$1") (pin "4") (pinfunction "AGND1_4") (pintype "bidirectional"))
      (node (ref "U$1") (pin "41") (pinfunction "AGND3_41") (pintype "bidirectional"))
      (node (ref "U$1") (pin "42") (pinfunction "TEST_42") (pintype "bidirectional"))
      (node (ref "U$1") (pin "47") (pinfunction "GND7_47") (pintype "bidirectional"))
      (node (ref "U$1") (pin "48") (pinfunction "GND8_48") (pintype "bidirectional"))
      (node (ref "U$1") (pin "9") (pinfunction "AGND2_9") (pintype "bidirectional"))
      (node (ref "U$2") (pin "1") (pinfunction "PWRDN_1") (pintype "bidirectional"))
      (node (ref "U$2") (pin "16") (pinfunction "GND2_16") (pintype "bidirectional"))
      (node (ref "U$3") (pin "5") (pinfunction "GND_5") (pintype "bidirectional"))
      (node (ref "U$4") (pin "1") (pinfunction "GND_1") (pintype "bidirectional"))
      (node (ref "U$5") (pin "1") (pinfunction "GND_1") (pintype "bidirectional"))
      (node (ref "U$6") (pin "1") (pinfunction "PWRDN_1") (pintype "bidirectional"))
      (node (ref "U$6") (pin "16") (pinfunction "GND2_16") (pintype "bidirectional"))
      (node (ref "U$7") (pin "12") (pinfunction "GND_12") (pintype "bidirectional"))
      (node (ref "U$7") (pin "30") (pinfunction "GND2_30") (pintype "bidirectional"))
      (node (ref "U$8") (pin "NET2") (pinfunction "NET2_NET2") (pintype "bidirectional"))
      (node (ref "X1") (pin "4") (pinfunction "4_4") (pintype "passive"))
    )
    (net (code "81") (name "Net-(C51-Pad1)") (class "Default")
      (node (ref "C51") (pin "1") (pinfunction "1_1") (pintype "passive"))
      (node (ref "R19") (pin "1") (pinfunction "1_1") (pintype "passive"))
      (node (ref "X2") (pin "1") (pinfunction "1_1") (pintype "passive"))
    )
    (net (code "82") (name "Net-(C58-Pad1)") (class "Default")
      (node (ref "C58") (pin "1") (pinfunction "1_1") (pintype "passive"))
      (node (ref "R30") (pin "1") (pinfunction "1_1") (pintype "passive"))
      (node (ref "X3") (pin "1") (pinfunction "1_1") (pintype "passive"))
    )
    (net (code "83") (name "Net-(CONFIG_FLASH-DATA)") (class "Default")
      (node (ref "CONFIG_FLASH") (pin "2") (pinfunction "DATA_2") (pintype "bidirectional"))
      (node (ref "R12") (pin "2") (pinfunction "2_2") (pintype "passive"))
    )
    (net (code "84") (name "Net-(D1-COM)") (class "Default")
      (node (ref "D1") (pin "3") (pinfunction "COM_3") (pintype "bidirectional"))
      (node (ref "R3") (pin "2") (pinfunction "2_2") (pintype "passive"))
      (node (ref "X1") (pin "2") (pinfunction "2_2") (pintype "passive"))
    )
    (net (code "85") (name "Net-(D2-COM)") (class "Default")
      (node (ref "D2") (pin "3") (pinfunction "COM_3") (pintype "bidirectional"))
      (node (ref "R4") (pin "2") (pinfunction "2_2") (pintype "passive"))
      (node (ref "X1") (pin "3") (pinfunction "3_3") (pintype "passive"))
    )
    (net (code "86") (name "Net-(D3-C)") (class "Default")
      (node (ref "D3") (pin "2") (pinfunction "C_2") (pintype "passive"))
      (node (ref "EXT_5V") (pin "1") (pinfunction "1_1") (pintype "passive"))
    )
    (net (code "87") (name "Net-(D4-A)") (class "Default")
      (node (ref "D4") (pin "1") (pinfunction "A_1") (pintype "passive"))
      (node (ref "EXT_5V") (pin "2") (pinfunction "2_2") (pintype "passive"))
    )
    (net (code "88") (name "Net-(D5-A)") (class "Default")
      (node (ref "D5") (pin "1") (pinfunction "A_1") (pintype "passive"))
      (node (ref "POWER_SELECT") (pin "3") (pinfunction "3_3") (pintype "passive"))
    )
    (net (code "89") (name "Net-(IC1-CONF_DONE)") (class "Default")
      (node (ref "IC1") (pin "92") (pinfunction "CONF_DONE_92") (pintype "input"))
      (node (ref "R15") (pin "1") (pinfunction "1_1") (pintype "passive"))
    )
    (net (code "90") (name "Net-(IC1-NCONFIG)") (class "Default")
      (node (ref "IC1") (pin "14") (pinfunction "NCONFIG_14") (pintype "input"))
      (node (ref "R14") (pin "1") (pinfunction "1_1") (pintype "passive"))
    )
    (net (code "91") (name "Net-(IC1-NSTATUS)") (class "Default")
      (node (ref "IC1") (pin "9") (pinfunction "NSTATUS_9") (pintype "input"))
      (node (ref "R13") (pin "1") (pinfunction "1_1") (pintype "passive"))
    )
    (net (code "92") (name "Net-(IC2A-I)") (class "Default")
      (node (ref "C62") (pin "1") (pinfunction "1_1") (pintype "passive"))
      (node (ref "IC2") (pin "2") (pinfunction "I_2") (pintype "input"))
      (node (ref "R31") (pin "1") (pinfunction "1_1") (pintype "passive"))
      (node (ref "S1") (pin "1") (pinfunction "S_1") (pintype "passive"))
      (node (ref "S1") (pin "2") (pinfunction "S1_2") (pintype "passive"))
    )
    (net (code "93") (name "Net-(IC2A-O)") (class "Default")
      (node (ref "IC2") (pin "4") (pinfunction "O_4") (pintype "open_collector"))
      (node (ref "R33") (pin "1") (pinfunction "1_1") (pintype "passive"))
    )
    (net (code "94") (name "Net-(LED1-A)") (class "Default")
      (node (ref "LED1") (pin "1") (pinfunction "A_1") (pintype "passive"))
      (node (ref "R9") (pin "1") (pinfunction "1_1") (pintype "passive"))
    )
    (net (code "95") (name "Net-(LED2-A)") (class "Default")
      (node (ref "LED2") (pin "1") (pinfunction "A_1") (pintype "passive"))
      (node (ref "R10") (pin "1") (pinfunction "1_1") (pintype "passive"))
    )
    (net (code "96") (name "Net-(LED_1-A)") (class "Default")
      (node (ref "LED_1") (pin "1") (pinfunction "A_1") (pintype "passive"))
      (node (ref "R26") (pin "1") (pinfunction "1_1") (pintype "passive"))
    )
    (net (code "97") (name "Net-(LED_2-A)") (class "Default")
      (node (ref "LED_2") (pin "1") (pinfunction "A_1") (pintype "passive"))
      (node (ref "R27") (pin "1") (pinfunction "1_1") (pintype "passive"))
    )
    (net (code "98") (name "Net-(LED_3-A)") (class "Default")
      (node (ref "LED_3") (pin "1") (pinfunction "A_1") (pintype "passive"))
      (node (ref "R28") (pin "1") (pinfunction "1_1") (pintype "passive"))
    )
    (net (code "99") (name "Net-(LED_4-A)") (class "Default")
      (node (ref "LED_4") (pin "1") (pinfunction "A_1") (pintype "passive"))
      (node (ref "R29") (pin "1") (pinfunction "1_1") (pintype "passive"))
    )
    (net (code "100") (name "Net-(LS-IN)") (class "Default")
      (node (ref "C40") (pin "1") (pinfunction "1_1") (pintype "passive"))
      (node (ref "C41") (pin "1") (pinfunction "1_1") (pintype "passive"))
      (node (ref "L3") (pin "2") (pinfunction "2_2") (pintype "passive"))
      (node (ref "LS") (pin "3") (pinfunction "IN_3") (pintype "bidirectional"))
    )
    (net (code "101") (name "Net-(OSCILLATOR50_MHZ-OE)") (class "Default")
      (node (ref "C49") (pin "1") (pinfunction "1_1") (pintype "passive"))
      (node (ref "L6") (pin "2") (pinfunction "2_2") (pintype "passive"))
      (node (ref "OSCILLATOR50_MHZ") (pin "1") (pinfunction "OE_1") (pintype "bidirectional"))
      (node (ref "OSCILLATOR50_MHZ") (pin "4") (pinfunction "VCC_4") (pintype "bidirectional"))
    )
    (net (code "102") (name "Net-(U$1-ACBUS4)") (class "Default")
      (node (ref "R11") (pin "1") (pinfunction "1_1") (pintype "passive"))
      (node (ref "U$1") (pin "28") (pinfunction "ACBUS4_28") (pintype "bidirectional"))
    )
    (net (code "103") (name "Net-(U$1-DM)") (class "Default")
      (node (ref "R3") (pin "1") (pinfunction "1_1") (pintype "passive"))
      (node (ref "U$1") (pin "6") (pinfunction "DM_6") (pintype "bidirectional"))
    )
    (net (code "104") (name "Net-(U$1-DP)") (class "Default")
      (node (ref "R4") (pin "1") (pinfunction "1_1") (pintype "passive"))
      (node (ref "U$1") (pin "7") (pinfunction "DP_7") (pintype "bidirectional"))
    )
    (net (code "105") (name "Net-(U$1-EECLK)") (class "Default")
      (node (ref "R7") (pin "1") (pinfunction "1_1") (pintype "passive"))
      (node (ref "U$1") (pin "44") (pinfunction "EECLK_44") (pintype "bidirectional"))
      (node (ref "U$3") (pin "2") (pinfunction "CLK_2") (pintype "bidirectional"))
    )
    (net (code "106") (name "Net-(U$1-EECS)") (class "Default")
      (node (ref "R6") (pin "1") (pinfunction "1_1") (pintype "passive"))
      (node (ref "U$1") (pin "45") (pinfunction "EECS_45") (pintype "bidirectional"))
      (node (ref "U$3") (pin "1") (pinfunction "CS_1") (pintype "bidirectional"))
    )
    (net (code "107") (name "Net-(U$1-EEDATA)") (class "Default")
      (node (ref "R5") (pin "2") (pinfunction "2_2") (pintype "passive"))
      (node (ref "U$1") (pin "43") (pinfunction "EEDATA_43") (pintype "bidirectional"))
      (node (ref "U$3") (pin "3") (pinfunction "DI_3") (pintype "bidirectional"))
    )
    (net (code "108") (name "Net-(U$1-REF)") (class "Default")
      (node (ref "R1") (pin "2") (pinfunction "2_2") (pintype "passive"))
      (node (ref "U$1") (pin "5") (pinfunction "REF_5") (pintype "bidirectional"))
    )
    (net (code "109") (name "Net-(U$1-RESET)") (class "Default")
      (node (ref "C14") (pin "1") (pinfunction "1_1") (pintype "passive"))
      (node (ref "R2") (pin "1") (pinfunction "1_1") (pintype "passive"))
      (node (ref "U$1") (pin "34") (pinfunction "RESET_34") (pintype "bidirectional"))
    )
    (net (code "110") (name "Net-(U$1-VCCA)") (class "Default")
      (node (ref "C1") (pin "1") (pinfunction "1_1") (pintype "passive"))
      (node (ref "U$1") (pin "37") (pinfunction "VCCA_37") (pintype "bidirectional"))
    )
    (net (code "111") (name "Net-(U$1-VCCCORE)") (class "Default")
      (node (ref "C6") (pin "1") (pinfunction "1_1") (pintype "passive"))
      (node (ref "U$1") (pin "38") (pinfunction "VCCCORE_38") (pintype "bidirectional"))
    )
    (net (code "112") (name "Net-(U$1-VPHY)") (class "Default")
      (node (ref "C7") (pin "1") (pinfunction "1_1") (pintype "passive"))
      (node (ref "C8") (pin "1") (pinfunction "1_1") (pintype "passive"))
      (node (ref "L2") (pin "2") (pinfunction "2_2") (pintype "passive"))
      (node (ref "U$1") (pin "3") (pinfunction "VPHY_3") (pintype "bidirectional"))
    )
    (net (code "113") (name "Net-(U$1-VPLL)") (class "Default")
      (node (ref "C10") (pin "1") (pinfunction "1_1") (pintype "passive"))
      (node (ref "C9") (pin "1") (pinfunction "1_1") (pintype "passive"))
      (node (ref "L1") (pin "2") (pinfunction "2_2") (pintype "passive"))
      (node (ref "U$1") (pin "8") (pinfunction "VPLL_8") (pintype "bidirectional"))
    )
    (net (code "114") (name "Net-(U$1-XCSI)") (class "Default")
      (node (ref "C2") (pin "1") (pinfunction "1_1") (pintype "passive"))
      (node (ref "Q1") (pin "1") (pinfunction "1_1") (pintype "passive"))
      (node (ref "U$1") (pin "1") (pinfunction "XCSI_1") (pintype "bidirectional"))
    )
    (net (code "115") (name "Net-(U$1-XCSO)") (class "Default")
      (node (ref "C3") (pin "1") (pinfunction "1_1") (pintype "passive"))
      (node (ref "Q1") (pin "2") (pinfunction "2_2") (pintype "passive"))
      (node (ref "U$1") (pin "2") (pinfunction "XCSO_2") (pintype "bidirectional"))
    )
    (net (code "116") (name "Net-(U$2-AIN)") (class "Default")
      (node (ref "C58") (pin "2") (pinfunction "2_2") (pintype "passive"))
      (node (ref "U$2") (pin "6") (pinfunction "BIAS_OUT_6") (pintype "bidirectional"))
      (node (ref "U$2") (pin "7") (pinfunction "AIN_7") (pintype "bidirectional"))
    )
    (net (code "117") (name "Net-(U$2-VREF_IN)") (class "Default")
      (node (ref "C57") (pin "1") (pinfunction "1_1") (pintype "passive"))
      (node (ref "U$2") (pin "2") (pinfunction "VREF_OUT_2") (pintype "bidirectional"))
      (node (ref "U$2") (pin "3") (pinfunction "VREF_IN_3") (pintype "bidirectional"))
    )
    (net (code "118") (name "Net-(U$3-DO)") (class "Default")
      (node (ref "R5") (pin "1") (pinfunction "1_1") (pintype "passive"))
      (node (ref "R8") (pin "1") (pinfunction "1_1") (pintype "passive"))
      (node (ref "U$3") (pin "4") (pinfunction "DO_4") (pintype "bidirectional"))
    )
    (net (code "119") (name "Net-(U$4-IN)") (class "Default")
      (node (ref "C43") (pin "1") (pinfunction "1_1") (pintype "passive"))
      (node (ref "C44") (pin "1") (pinfunction "1_1") (pintype "passive"))
      (node (ref "L4") (pin "2") (pinfunction "2_2") (pintype "passive"))
      (node (ref "U$4") (pin "3") (pinfunction "IN_3") (pintype "bidirectional"))
    )
    (net (code "120") (name "Net-(U$5-IN)") (class "Default")
      (node (ref "C46") (pin "1") (pinfunction "1_1") (pintype "passive"))
      (node (ref "C47") (pin "1") (pinfunction "1_1") (pintype "passive"))
      (node (ref "L5") (pin "2") (pinfunction "2_2") (pintype "passive"))
      (node (ref "U$5") (pin "3") (pinfunction "IN_3") (pintype "bidirectional"))
    )
    (net (code "121") (name "Net-(U$6-AIN)") (class "Default")
      (node (ref "C51") (pin "2") (pinfunction "2_2") (pintype "passive"))
      (node (ref "U$6") (pin "6") (pinfunction "BIAS_OUT_6") (pintype "bidirectional"))
      (node (ref "U$6") (pin "7") (pinfunction "AIN_7") (pintype "bidirectional"))
    )
    (net (code "122") (name "Net-(U$6-VREF_IN)") (class "Default")
      (node (ref "C50") (pin "1") (pinfunction "1_1") (pintype "passive"))
      (node (ref "U$6") (pin "2") (pinfunction "VREF_OUT_2") (pintype "bidirectional"))
      (node (ref "U$6") (pin "3") (pinfunction "VREF_IN_3") (pintype "bidirectional"))
    )
    (net (code "123") (name "unconnected-(IC1-CLK0-Pad22)") (class "Default")
      (node (ref "IC1") (pin "22") (pinfunction "CLK0_22") (pintype "passive"))
    )
    (net (code "124") (name "unconnected-(IC1-CLK1-Pad23)") (class "Default")
      (node (ref "IC1") (pin "23") (pinfunction "CLK1_23") (pintype "passive"))
    )
    (net (code "125") (name "unconnected-(IC1-CLK2-Pad24)") (class "Default")
      (node (ref "IC1") (pin "24") (pinfunction "CLK2_24") (pintype "passive"))
    )
    (net (code "126") (name "unconnected-(IC1-CLK5-Pad90)") (class "Default")
      (node (ref "IC1") (pin "90") (pinfunction "CLK5_90") (pintype "passive"))
    )
    (net (code "127") (name "unconnected-(IC1-CLK6-Pad89)") (class "Default")
      (node (ref "IC1") (pin "89") (pinfunction "CLK6_89") (pintype "passive"))
    )
    (net (code "128") (name "unconnected-(IC1-IO7-Pad7)") (class "Default")
      (node (ref "IC1") (pin "7") (pinfunction "IO7_7") (pintype "output"))
    )
    (net (code "129") (name "unconnected-(IC1-IO10-Pad10)") (class "Default")
      (node (ref "IC1") (pin "10") (pinfunction "IO10_10") (pintype "bidirectional"))
    )
    (net (code "130") (name "unconnected-(IC1-IO11-Pad11)") (class "Default")
      (node (ref "IC1") (pin "11") (pinfunction "IO11_11") (pintype "bidirectional"))
    )
    (net (code "131") (name "unconnected-(IC1-IO28-Pad28)") (class "Default")
      (node (ref "IC1") (pin "28") (pinfunction "IO28_28") (pintype "bidirectional"))
    )
    (net (code "132") (name "unconnected-(IC1-IO39-Pad39)") (class "Default")
      (node (ref "IC1") (pin "39") (pinfunction "IO39_39") (pintype "bidirectional"))
    )
    (net (code "133") (name "unconnected-(IC1-IO42-Pad42)") (class "Default")
      (node (ref "IC1") (pin "42") (pinfunction "IO42_42") (pintype "bidirectional"))
    )
    (net (code "134") (name "unconnected-(IC1-IO46-Pad46)") (class "Default")
      (node (ref "IC1") (pin "46") (pinfunction "IO46_46") (pintype "bidirectional"))
    )
    (net (code "135") (name "unconnected-(IC1-IO49-Pad49)") (class "Default")
      (node (ref "IC1") (pin "49") (pinfunction "IO49_49") (pintype "bidirectional"))
    )
    (net (code "136") (name "unconnected-(IC1-IO55-Pad55)") (class "Default")
      (node (ref "IC1") (pin "55") (pinfunction "IO55_55") (pintype "bidirectional"))
    )
    (net (code "137") (name "unconnected-(IC1-IO58-Pad58)") (class "Default")
      (node (ref "IC1") (pin "58") (pinfunction "IO58_58") (pintype "bidirectional"))
    )
    (net (code "138") (name "unconnected-(IC1-IO80-Pad80)") (class "Default")
      (node (ref "IC1") (pin "80") (pinfunction "IO80_80") (pintype "bidirectional"))
    )
    (net (code "139") (name "unconnected-(IC1-IO83-Pad83)") (class "Default")
      (node (ref "IC1") (pin "83") (pinfunction "IO83_83") (pintype "bidirectional"))
    )
    (net (code "140") (name "unconnected-(IC1-IO110-Pad110)") (class "Default")
      (node (ref "IC1") (pin "110") (pinfunction "IO110_110") (pintype "bidirectional"))
    )
    (net (code "141") (name "unconnected-(IC1-IO111-Pad111)") (class "Default")
      (node (ref "IC1") (pin "111") (pinfunction "IO111_111") (pintype "bidirectional"))
    )
    (net (code "142") (name "unconnected-(IC1-IO121-Pad121)") (class "Default")
      (node (ref "IC1") (pin "121") (pinfunction "IO121_121") (pintype "bidirectional"))
    )
    (net (code "143") (name "unconnected-(IC1-IO124-Pad124)") (class "Default")
      (node (ref "IC1") (pin "124") (pinfunction "IO124_124") (pintype "bidirectional"))
    )
    (net (code "144") (name "unconnected-(IC1-IO129-Pad129)") (class "Default")
      (node (ref "IC1") (pin "129") (pinfunction "IO129_129") (pintype "bidirectional"))
    )
    (net (code "145") (name "unconnected-(IC1-IO132-Pad132)") (class "Default")
      (node (ref "IC1") (pin "132") (pinfunction "IO132_132") (pintype "bidirectional"))
    )
    (net (code "146") (name "unconnected-(IC1-IO135-Pad135)") (class "Default")
      (node (ref "IC1") (pin "135") (pinfunction "IO135_135") (pintype "bidirectional"))
    )
    (net (code "147") (name "unconnected-(IC1-IO136-Pad136)") (class "Default")
      (node (ref "IC1") (pin "136") (pinfunction "IO136_136") (pintype "bidirectional"))
    )
    (net (code "148") (name "unconnected-(IC1-IO137-Pad137)") (class "Default")
      (node (ref "IC1") (pin "137") (pinfunction "IO137_137") (pintype "bidirectional"))
    )
    (net (code "149") (name "unconnected-(IC1-IO138-Pad138)") (class "Default")
      (node (ref "IC1") (pin "138") (pinfunction "IO138_138") (pintype "bidirectional"))
    )
    (net (code "150") (name "unconnected-(IC1-IO141-Pad141)") (class "Default")
      (node (ref "IC1") (pin "141") (pinfunction "IO141_141") (pintype "bidirectional"))
    )
    (net (code "151") (name "unconnected-(IC1-IO142-Pad142)") (class "Default")
      (node (ref "IC1") (pin "142") (pinfunction "IO142_142") (pintype "bidirectional"))
    )
    (net (code "152") (name "unconnected-(IC1-IO143-Pad143)") (class "Default")
      (node (ref "IC1") (pin "143") (pinfunction "IO143_143") (pintype "bidirectional"))
    )
    (net (code "153") (name "unconnected-(IC1-IO144-Pad144)") (class "Default")
      (node (ref "IC1") (pin "144") (pinfunction "IO144_144") (pintype "bidirectional"))
    )
    (net (code "154") (name "unconnected-(JTAG-Pad6)") (class "Default")
      (node (ref "JTAG") (pin "6") (pinfunction "6_6") (pintype "passive"))
    )
    (net (code "155") (name "unconnected-(JTAG-Pad7)") (class "Default")
      (node (ref "JTAG") (pin "7") (pinfunction "7_7") (pintype "passive"))
    )
    (net (code "156") (name "unconnected-(JTAG-Pad8)") (class "Default")
      (node (ref "JTAG") (pin "8") (pinfunction "8_8") (pintype "passive"))
    )
    (net (code "157") (name "unconnected-(U$7-CLKIN1-Pad3)") (class "Default")
      (node (ref "U$7") (pin "3") (pinfunction "CLKIN1_3") (pintype "bidirectional"))
    )
    (net (code "158") (name "unconnected-(U$7-D15-Pad22)") (class "Default")
      (node (ref "U$7") (pin "22") (pinfunction "D15_22") (pintype "bidirectional"))
    )
    (net (code "159") (name "unconnected-(U$7-D16-Pad23)") (class "Default")
      (node (ref "U$7") (pin "23") (pinfunction "D16_23") (pintype "bidirectional"))
    )
    (net (code "160") (name "unconnected-(U$7-D17-Pad24)") (class "Default")
      (node (ref "U$7") (pin "24") (pinfunction "D17_24") (pintype "bidirectional"))
    )
    (net (code "161") (name "unconnected-(U$7-D18-Pad25)") (class "Default")
      (node (ref "U$7") (pin "25") (pinfunction "D18_25") (pintype "bidirectional"))
    )
    (net (code "162") (name "unconnected-(U$7-D19-Pad26)") (class "Default")
      (node (ref "U$7") (pin "26") (pinfunction "D19_26") (pintype "bidirectional"))
    )
    (net (code "163") (name "unconnected-(U$7-D20-Pad27)") (class "Default")
      (node (ref "U$7") (pin "27") (pinfunction "D20_27") (pintype "bidirectional"))
    )
    (net (code "164") (name "unconnected-(U$7-D21-Pad28)") (class "Default")
      (node (ref "U$7") (pin "28") (pinfunction "D21_28") (pintype "bidirectional"))
    )
    (net (code "165") (name "unconnected-(U$7-D22-Pad31)") (class "Default")
      (node (ref "U$7") (pin "31") (pinfunction "D22_31") (pintype "bidirectional"))
    )
    (net (code "166") (name "unconnected-(U$7-D23-Pad32)") (class "Default")
      (node (ref "U$7") (pin "32") (pinfunction "D23_32") (pintype "bidirectional"))
    )
    (net (code "167") (name "unconnected-(U$7-D24-Pad33)") (class "Default")
      (node (ref "U$7") (pin "33") (pinfunction "D24_33") (pintype "bidirectional"))
    )
    (net (code "168") (name "unconnected-(U$7-D25-Pad34)") (class "Default")
      (node (ref "U$7") (pin "34") (pinfunction "D25_34") (pintype "bidirectional"))
    )
    (net (code "169") (name "unconnected-(U$7-D26-Pad35)") (class "Default")
      (node (ref "U$7") (pin "35") (pinfunction "D26_35") (pintype "bidirectional"))
    )
    (net (code "170") (name "unconnected-(U$7-D27-Pad36)") (class "Default")
      (node (ref "U$7") (pin "36") (pinfunction "D27_36") (pintype "bidirectional"))
    )
    (net (code "171") (name "unconnected-(U$7-D28-Pad37)") (class "Default")
      (node (ref "U$7") (pin "37") (pinfunction "D28_37") (pintype "bidirectional"))
    )
    (net (code "172") (name "unconnected-(U$7-D29-Pad38)") (class "Default")
      (node (ref "U$7") (pin "38") (pinfunction "D29_38") (pintype "bidirectional"))
    )
    (net (code "173") (name "unconnected-(U$7-D30-Pad39)") (class "Default")
      (node (ref "U$7") (pin "39") (pinfunction "D30_39") (pintype "bidirectional"))
    )
    (net (code "174") (name "unconnected-(U$7-D31-Pad40)") (class "Default")
      (node (ref "U$7") (pin "40") (pinfunction "D31_40") (pintype "bidirectional"))
    )
    (net (code "175") (name "unconnected-(X1-PadS1)") (class "Default")
      (node (ref "X1") (pin "S1") (pinfunction "S1_S1") (pintype "passive"))
    )
    (net (code "176") (name "unconnected-(X1-PadS2)") (class "Default")
      (node (ref "X1") (pin "S2") (pinfunction "S2_S2") (pintype "passive"))
    )
  )
)
